# i2c_encoder_5.net
KiCad netlist of a schematic drawn in EAGLE
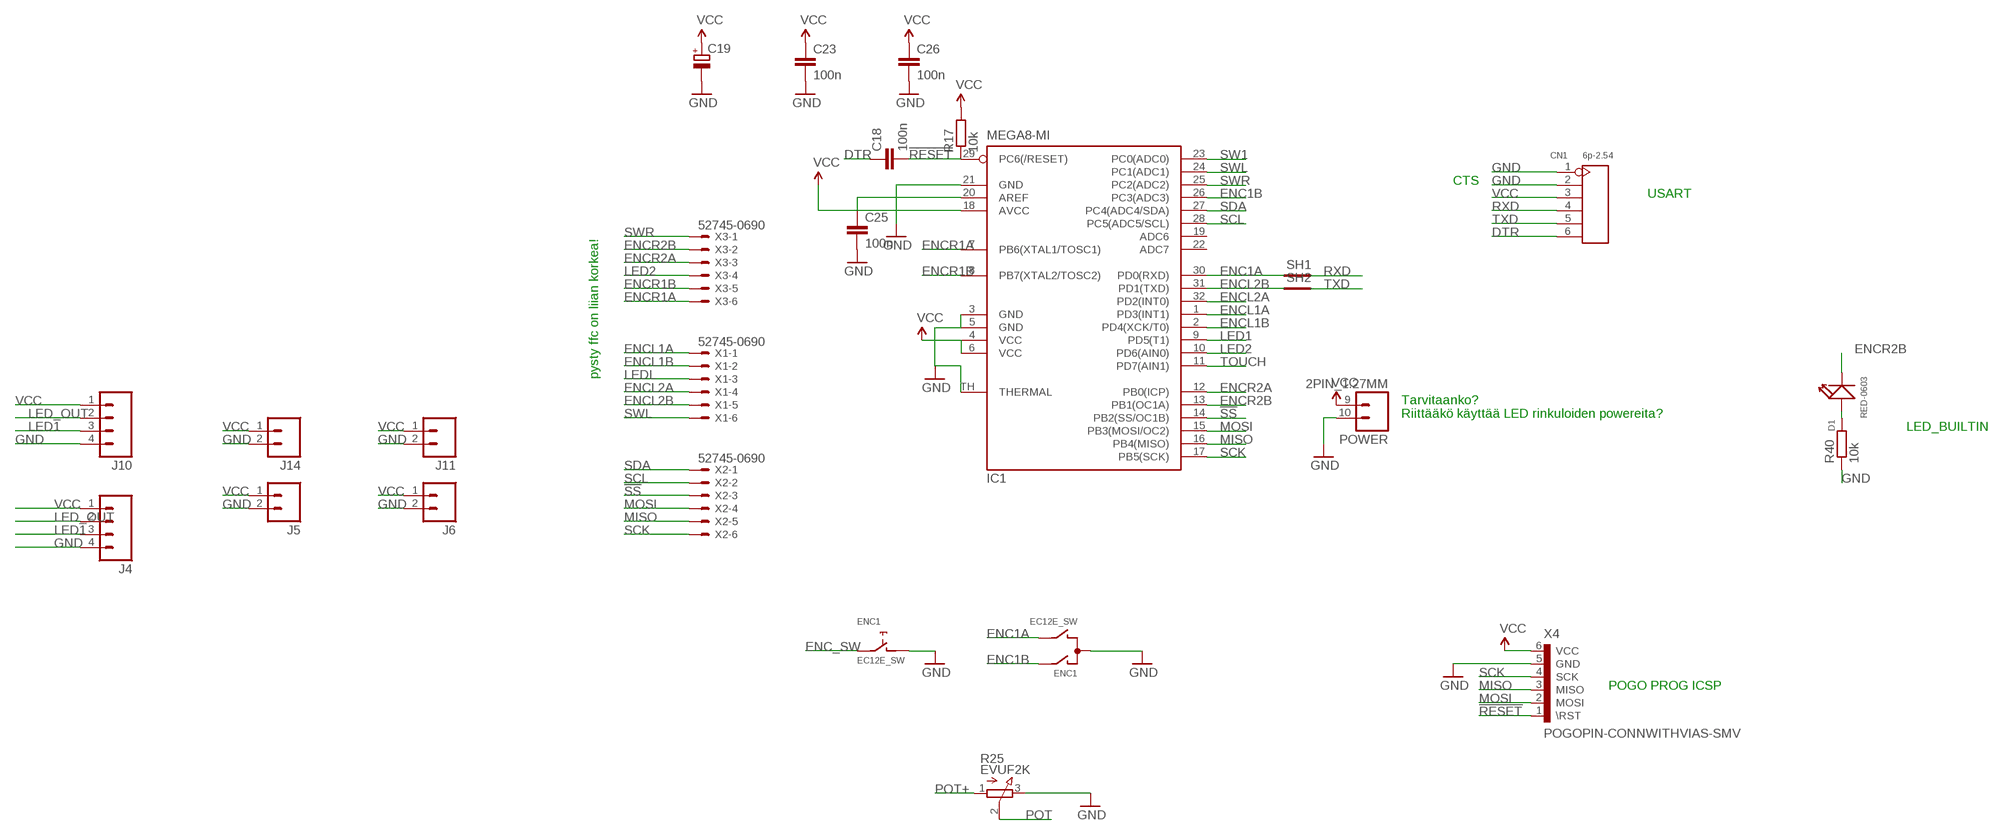
[diagram p0: schematic, sheet 1]
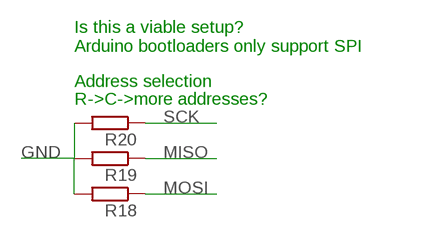
[diagram p1: schematic, sheet 2]
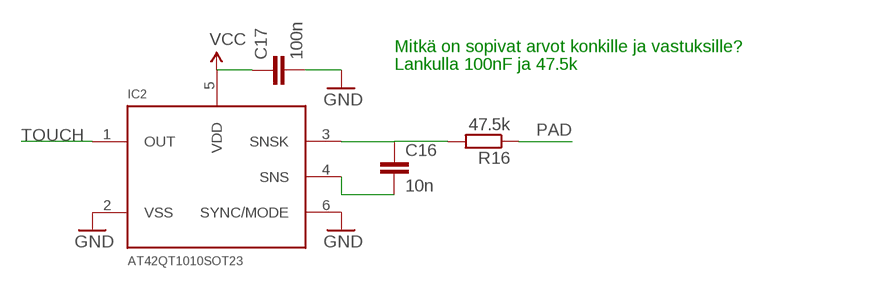
[diagram p2: schematic, sheet 3]
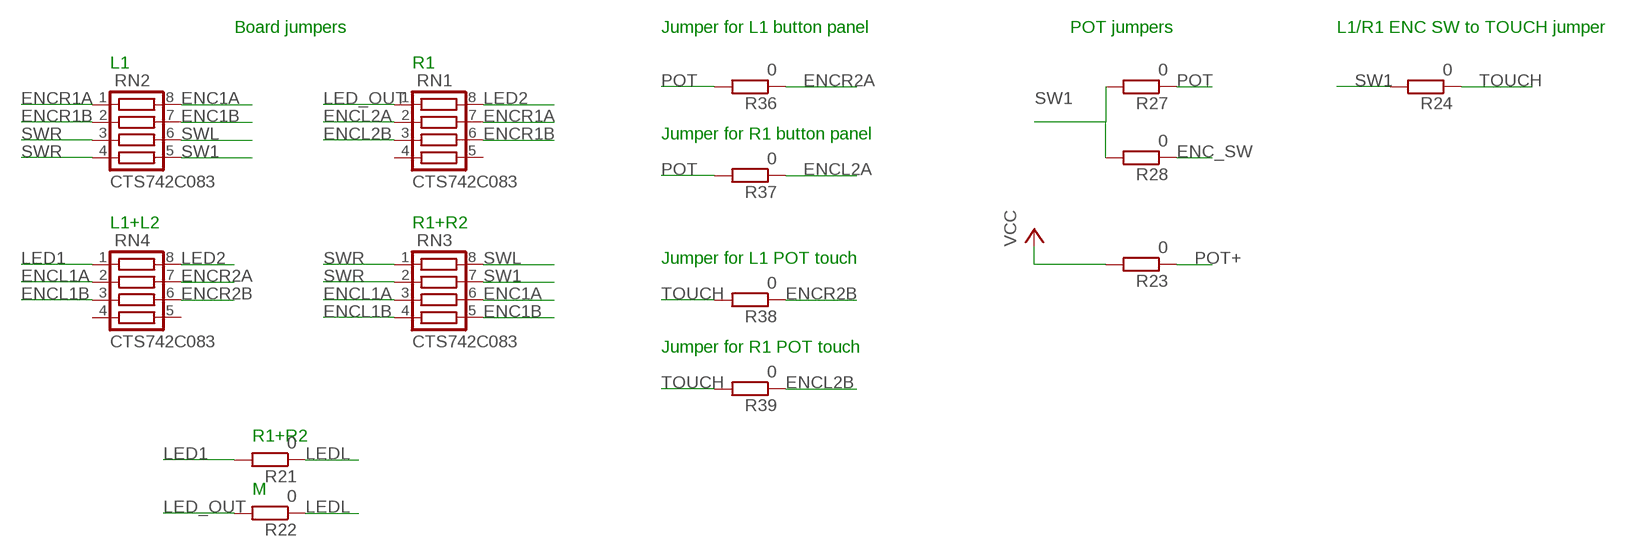
[diagram p3: schematic, sheet 4]
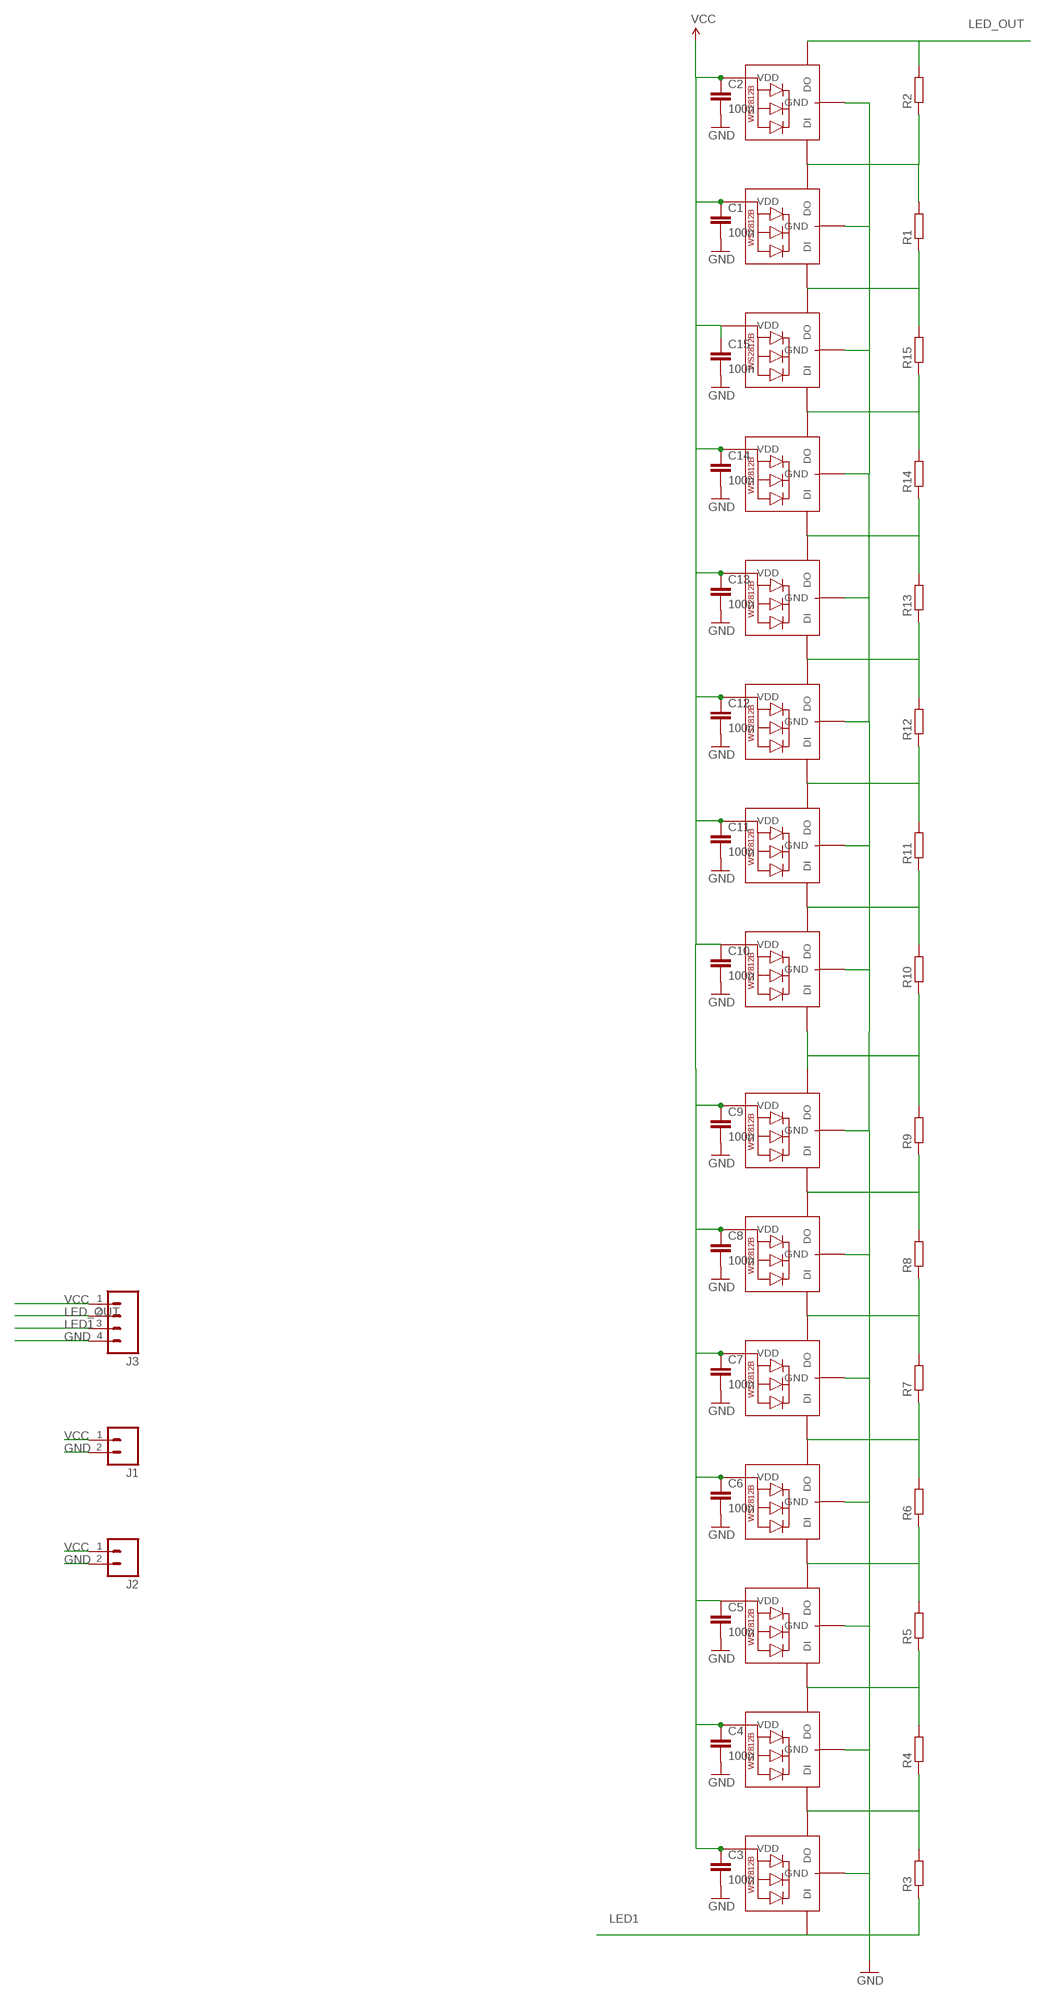
[diagram p4: schematic, sheet 5]
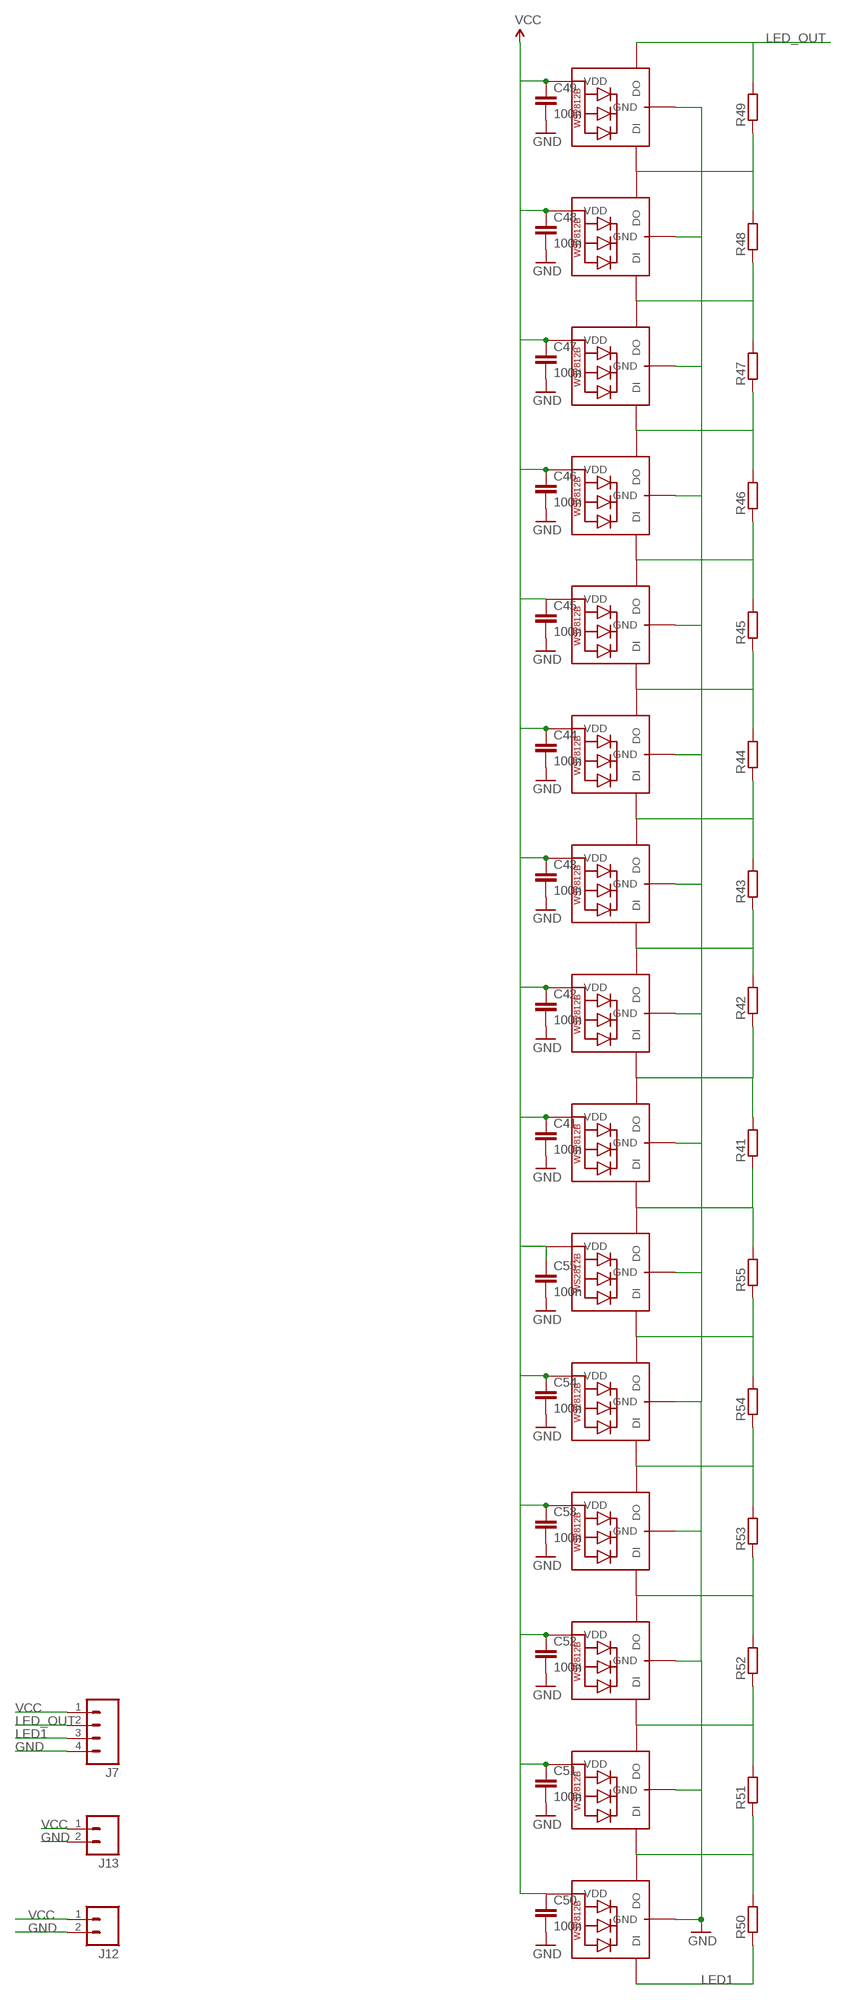
[diagram p5: schematic, sheet 6]
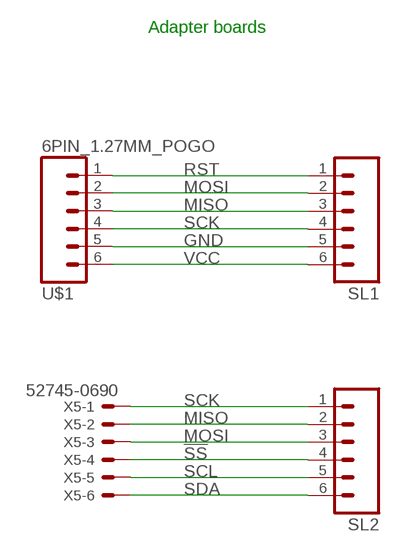
[diagram p6: schematic, sheet 7]
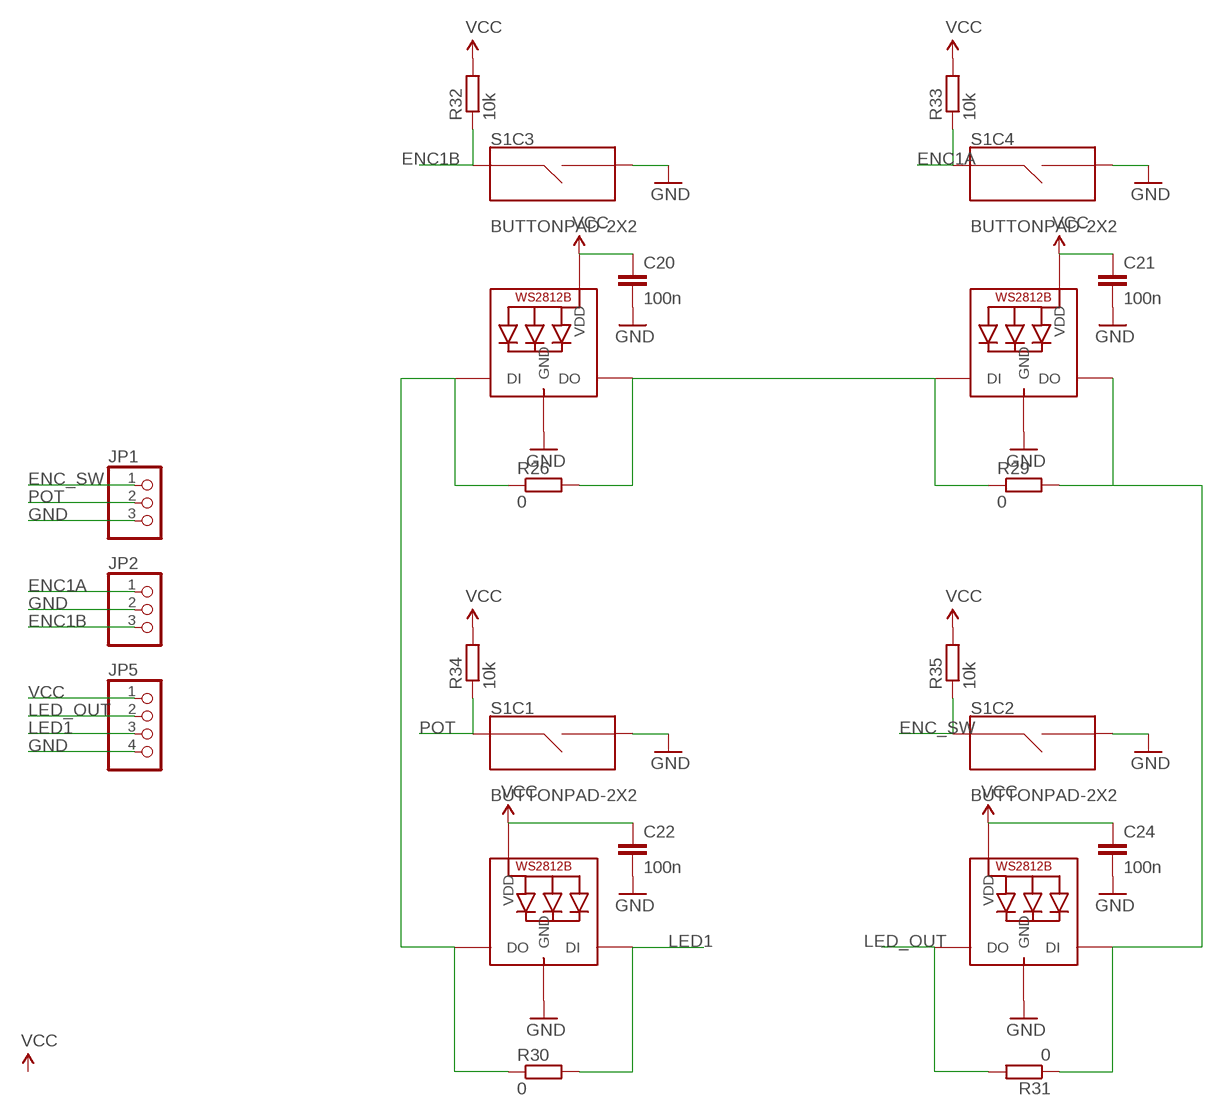
[diagram p7: schematic, sheet 8]

(export (version "E")
  (design (tool "Eeschema 10.0.6"))
  (components
    (comp (ref "R18")
      (value "R-EU_R0603")
      (footprint "eagle-import:R0603")
      (libsource (lib "eagle-import") (part "R-EU_R0603"))
    )
    (comp (ref "R19")
      (value "R-EU_R0603")
      (footprint "eagle-import:R0603")
      (libsource (lib "eagle-import") (part "R-EU_R0603"))
    )
    (comp (ref "R20")
      (value "R-EU_R0603")
      (footprint "eagle-import:R0603")
      (libsource (lib "eagle-import") (part "R-EU_R0603"))
    )
    (comp (ref "C41")
      (value "100n")
      (footprint "eagle-import:0603-CAP")
      (libsource (lib "eagle-import") (part "CAP0603-CAP"))
    )
    (comp (ref "C42")
      (value "100n")
      (footprint "eagle-import:0603-CAP")
      (libsource (lib "eagle-import") (part "CAP0603-CAP"))
    )
    (comp (ref "C43")
      (value "100n")
      (footprint "eagle-import:0603-CAP")
      (libsource (lib "eagle-import") (part "CAP0603-CAP"))
    )
    (comp (ref "C44")
      (value "100n")
      (footprint "eagle-import:0603-CAP")
      (libsource (lib "eagle-import") (part "CAP0603-CAP"))
    )
    (comp (ref "C45")
      (value "100n")
      (footprint "eagle-import:0603-CAP")
      (libsource (lib "eagle-import") (part "CAP0603-CAP"))
    )
    (comp (ref "C46")
      (value "100n")
      (footprint "eagle-import:0603-CAP")
      (libsource (lib "eagle-import") (part "CAP0603-CAP"))
    )
    (comp (ref "C47")
      (value "100n")
      (footprint "eagle-import:0603-CAP")
      (libsource (lib "eagle-import") (part "CAP0603-CAP"))
    )
    (comp (ref "C48")
      (value "100n")
      (footprint "eagle-import:0603-CAP")
      (libsource (lib "eagle-import") (part "CAP0603-CAP"))
    )
    (comp (ref "C49")
      (value "100n")
      (footprint "eagle-import:0603-CAP")
      (libsource (lib "eagle-import") (part "CAP0603-CAP"))
    )
    (comp (ref "C50")
      (value "100n")
      (footprint "eagle-import:0603-CAP")
      (libsource (lib "eagle-import") (part "CAP0603-CAP"))
    )
    (comp (ref "C51")
      (value "100n")
      (footprint "eagle-import:0603-CAP")
      (libsource (lib "eagle-import") (part "CAP0603-CAP"))
    )
    (comp (ref "C52")
      (value "100n")
      (footprint "eagle-import:0603-CAP")
      (libsource (lib "eagle-import") (part "CAP0603-CAP"))
    )
    (comp (ref "C53")
      (value "100n")
      (footprint "eagle-import:0603-CAP")
      (libsource (lib "eagle-import") (part "CAP0603-CAP"))
    )
    (comp (ref "C54")
      (value "100n")
      (footprint "eagle-import:0603-CAP")
      (libsource (lib "eagle-import") (part "CAP0603-CAP"))
    )
    (comp (ref "C55")
      (value "100n")
      (footprint "eagle-import:0603-CAP")
      (libsource (lib "eagle-import") (part "CAP0603-CAP"))
    )
    (comp (ref "J7")
      (value "M04NO_SILK_ALL_ROUND")
      (footprint "eagle-import:1X04_NO_SILK_ALL_ROUND")
      (libsource (lib "eagle-import") (part "M04NO_SILK_ALL_ROUND"))
    )
    (comp (ref "J12")
      (value "M021X02_NO_SILK")
      (footprint "eagle-import:1X02_NO_SILK")
      (libsource (lib "eagle-import") (part "M021X02_NO_SILK"))
    )
    (comp (ref "J13")
      (value "M021X02_NO_SILK")
      (footprint "eagle-import:1X02_NO_SILK")
      (libsource (lib "eagle-import") (part "M021X02_NO_SILK"))
    )
    (comp (ref "LED31")
      (value "WS2812B3535")
      (footprint "eagle-import:LED3535")
      (libsource (lib "eagle-import") (part "WS2812B3535"))
    )
    (comp (ref "LED32")
      (value "WS2812B3535")
      (footprint "eagle-import:LED3535")
      (libsource (lib "eagle-import") (part "WS2812B3535"))
    )
    (comp (ref "LED33")
      (value "WS2812B3535")
      (footprint "eagle-import:LED3535")
      (libsource (lib "eagle-import") (part "WS2812B3535"))
    )
    (comp (ref "LED34")
      (value "WS2812B3535")
      (footprint "eagle-import:LED3535")
      (libsource (lib "eagle-import") (part "WS2812B3535"))
    )
    (comp (ref "LED35")
      (value "WS2812B3535")
      (footprint "eagle-import:LED3535")
      (libsource (lib "eagle-import") (part "WS2812B3535"))
    )
    (comp (ref "LED36")
      (value "WS2812B3535")
      (footprint "eagle-import:LED3535")
      (libsource (lib "eagle-import") (part "WS2812B3535"))
    )
    (comp (ref "LED37")
      (value "WS2812B3535")
      (footprint "eagle-import:LED3535")
      (libsource (lib "eagle-import") (part "WS2812B3535"))
    )
    (comp (ref "LED38")
      (value "WS2812B3535")
      (footprint "eagle-import:LED3535")
      (libsource (lib "eagle-import") (part "WS2812B3535"))
    )
    (comp (ref "LED39")
      (value "WS2812B3535")
      (footprint "eagle-import:LED3535")
      (libsource (lib "eagle-import") (part "WS2812B3535"))
    )
    (comp (ref "LED40")
      (value "WS2812B3535")
      (footprint "eagle-import:LED3535")
      (libsource (lib "eagle-import") (part "WS2812B3535"))
    )
    (comp (ref "LED41")
      (value "WS2812B3535")
      (footprint "eagle-import:LED3535")
      (libsource (lib "eagle-import") (part "WS2812B3535"))
    )
    (comp (ref "LED42")
      (value "WS2812B3535")
      (footprint "eagle-import:LED3535")
      (libsource (lib "eagle-import") (part "WS2812B3535"))
    )
    (comp (ref "LED43")
      (value "WS2812B3535")
      (footprint "eagle-import:LED3535")
      (libsource (lib "eagle-import") (part "WS2812B3535"))
    )
    (comp (ref "LED44")
      (value "WS2812B3535")
      (footprint "eagle-import:LED3535")
      (libsource (lib "eagle-import") (part "WS2812B3535"))
    )
    (comp (ref "LED45")
      (value "WS2812B3535")
      (footprint "eagle-import:LED3535")
      (libsource (lib "eagle-import") (part "WS2812B3535"))
    )
    (comp (ref "R41")
      (value "R-EU_R0603")
      (footprint "eagle-import:R0603")
      (libsource (lib "eagle-import") (part "R-EU_R0603"))
    )
    (comp (ref "R42")
      (value "R-EU_R0603")
      (footprint "eagle-import:R0603")
      (libsource (lib "eagle-import") (part "R-EU_R0603"))
    )
    (comp (ref "R43")
      (value "R-EU_R0603")
      (footprint "eagle-import:R0603")
      (libsource (lib "eagle-import") (part "R-EU_R0603"))
    )
    (comp (ref "R44")
      (value "R-EU_R0603")
      (footprint "eagle-import:R0603")
      (libsource (lib "eagle-import") (part "R-EU_R0603"))
    )
    (comp (ref "R45")
      (value "R-EU_R0603")
      (footprint "eagle-import:R0603")
      (libsource (lib "eagle-import") (part "R-EU_R0603"))
    )
    (comp (ref "R46")
      (value "R-EU_R0603")
      (footprint "eagle-import:R0603")
      (libsource (lib "eagle-import") (part "R-EU_R0603"))
    )
    (comp (ref "R47")
      (value "R-EU_R0603")
      (footprint "eagle-import:R0603")
      (libsource (lib "eagle-import") (part "R-EU_R0603"))
    )
    (comp (ref "R48")
      (value "R-EU_R0603")
      (footprint "eagle-import:R0603")
      (libsource (lib "eagle-import") (part "R-EU_R0603"))
    )
    (comp (ref "R49")
      (value "R-EU_R0603")
      (footprint "eagle-import:R0603")
      (libsource (lib "eagle-import") (part "R-EU_R0603"))
    )
    (comp (ref "R50")
      (value "R-EU_R0603")
      (footprint "eagle-import:R0603")
      (libsource (lib "eagle-import") (part "R-EU_R0603"))
    )
    (comp (ref "R51")
      (value "R-EU_R0603")
      (footprint "eagle-import:R0603")
      (libsource (lib "eagle-import") (part "R-EU_R0603"))
    )
    (comp (ref "R52")
      (value "R-EU_R0603")
      (footprint "eagle-import:R0603")
      (libsource (lib "eagle-import") (part "R-EU_R0603"))
    )
    (comp (ref "R53")
      (value "R-EU_R0603")
      (footprint "eagle-import:R0603")
      (libsource (lib "eagle-import") (part "R-EU_R0603"))
    )
    (comp (ref "R54")
      (value "R-EU_R0603")
      (footprint "eagle-import:R0603")
      (libsource (lib "eagle-import") (part "R-EU_R0603"))
    )
    (comp (ref "R55")
      (value "R-EU_R0603")
      (footprint "eagle-import:R0603")
      (libsource (lib "eagle-import") (part "R-EU_R0603"))
    )
    (comp (ref "C16")
      (value "10n")
      (footprint "eagle-import:0603-CAP")
      (libsource (lib "eagle-import") (part "CAP0603-CAP"))
    )
    (comp (ref "C17")
      (value "100n")
      (footprint "eagle-import:0603-CAP")
      (libsource (lib "eagle-import") (part "CAP0603-CAP"))
    )
    (comp (ref "IC2")
      (value "AT42QT1010SOT23")
      (footprint "eagle-import:SOT23-6")
      (libsource (lib "eagle-import") (part "AT42QT1010SOT23"))
    )
    (comp (ref "R16")
      (value "47.5k")
      (footprint "eagle-import:R0603")
      (libsource (lib "eagle-import") (part "R-EU_R0603"))
    )
    (comp (ref "R21")
      (value "0")
      (footprint "eagle-import:R0603")
      (libsource (lib "eagle-import") (part "R-EU_R0603"))
    )
    (comp (ref "R22")
      (value "0")
      (footprint "eagle-import:R0603")
      (fields (field (name "SPICEPREFIX") "R"))
      (libsource (lib "eagle-import") (part "R-EU_R0603"))
    )
    (comp (ref "R23")
      (value "0")
      (footprint "eagle-import:R0603")
      (fields (field (name "SPICEPREFIX") "R"))
      (libsource (lib "eagle-import") (part "R-EU_R0603"))
    )
    (comp (ref "R24")
      (value "0")
      (footprint "eagle-import:R0603")
      (fields (field (name "SPICEPREFIX") "R"))
      (libsource (lib "eagle-import") (part "R-EU_R0603"))
    )
    (comp (ref "R27")
      (value "0")
      (footprint "eagle-import:R0603")
      (fields (field (name "SPICEPREFIX") "R"))
      (libsource (lib "eagle-import") (part "R-EU_R0603"))
    )
    (comp (ref "R28")
      (value "0")
      (footprint "eagle-import:R0603")
      (fields (field (name "SPICEPREFIX") "R"))
      (libsource (lib "eagle-import") (part "R-EU_R0603"))
    )
    (comp (ref "R36")
      (value "0")
      (footprint "eagle-import:R0603")
      (fields (field (name "SPICEPREFIX") "R"))
      (libsource (lib "eagle-import") (part "R-EU_R0603"))
    )
    (comp (ref "R37")
      (value "0")
      (footprint "eagle-import:R0603")
      (fields (field (name "SPICEPREFIX") "R"))
      (libsource (lib "eagle-import") (part "R-EU_R0603"))
    )
    (comp (ref "R38")
      (value "0")
      (footprint "eagle-import:R0603")
      (fields (field (name "SPICEPREFIX") "R"))
      (libsource (lib "eagle-import") (part "R-EU_R0603"))
    )
    (comp (ref "R39")
      (value "0")
      (footprint "eagle-import:R0603")
      (fields (field (name "SPICEPREFIX") "R"))
      (libsource (lib "eagle-import") (part "R-EU_R0603"))
    )
    (comp (ref "RN1")
      (value "CTS742C083")
      (footprint "eagle-import:CTS742C083")
      (libsource (lib "eagle-import") (part "CTS742C083"))
    )
    (comp (ref "RN2")
      (value "CTS742C083")
      (footprint "eagle-import:CTS742C083")
      (libsource (lib "eagle-import") (part "CTS742C083"))
    )
    (comp (ref "RN3")
      (value "CTS742C083")
      (footprint "eagle-import:CTS742C083")
      (libsource (lib "eagle-import") (part "CTS742C083"))
    )
    (comp (ref "RN4")
      (value "CTS742C083")
      (footprint "eagle-import:CTS742C083")
      (libsource (lib "eagle-import") (part "CTS742C083"))
    )
    (comp (ref "C1")
      (value "100n")
      (footprint "eagle-import:0603-CAP")
      (libsource (lib "eagle-import") (part "CAP0603-CAP"))
    )
    (comp (ref "C2")
      (value "100n")
      (footprint "eagle-import:0603-CAP")
      (libsource (lib "eagle-import") (part "CAP0603-CAP"))
    )
    (comp (ref "C3")
      (value "100n")
      (footprint "eagle-import:0603-CAP")
      (libsource (lib "eagle-import") (part "CAP0603-CAP"))
    )
    (comp (ref "C4")
      (value "100n")
      (footprint "eagle-import:0603-CAP")
      (libsource (lib "eagle-import") (part "CAP0603-CAP"))
    )
    (comp (ref "C5")
      (value "100n")
      (footprint "eagle-import:0603-CAP")
      (libsource (lib "eagle-import") (part "CAP0603-CAP"))
    )
    (comp (ref "C6")
      (value "100n")
      (footprint "eagle-import:0603-CAP")
      (libsource (lib "eagle-import") (part "CAP0603-CAP"))
    )
    (comp (ref "C7")
      (value "100n")
      (footprint "eagle-import:0603-CAP")
      (libsource (lib "eagle-import") (part "CAP0603-CAP"))
    )
    (comp (ref "C8")
      (value "100n")
      (footprint "eagle-import:0603-CAP")
      (libsource (lib "eagle-import") (part "CAP0603-CAP"))
    )
    (comp (ref "C9")
      (value "100n")
      (footprint "eagle-import:0603-CAP")
      (libsource (lib "eagle-import") (part "CAP0603-CAP"))
    )
    (comp (ref "C10")
      (value "100n")
      (footprint "eagle-import:0603-CAP")
      (libsource (lib "eagle-import") (part "CAP0603-CAP"))
    )
    (comp (ref "C11")
      (value "100n")
      (footprint "eagle-import:0603-CAP")
      (libsource (lib "eagle-import") (part "CAP0603-CAP"))
    )
    (comp (ref "C12")
      (value "100n")
      (footprint "eagle-import:0603-CAP")
      (libsource (lib "eagle-import") (part "CAP0603-CAP"))
    )
    (comp (ref "C13")
      (value "100n")
      (footprint "eagle-import:0603-CAP")
      (libsource (lib "eagle-import") (part "CAP0603-CAP"))
    )
    (comp (ref "C14")
      (value "100n")
      (footprint "eagle-import:0603-CAP")
      (libsource (lib "eagle-import") (part "CAP0603-CAP"))
    )
    (comp (ref "C15")
      (value "100n")
      (footprint "eagle-import:0603-CAP")
      (libsource (lib "eagle-import") (part "CAP0603-CAP"))
    )
    (comp (ref "J1")
      (value "M021X02_NO_SILK")
      (footprint "eagle-import:1X02_NO_SILK")
      (libsource (lib "eagle-import") (part "M021X02_NO_SILK"))
    )
    (comp (ref "J2")
      (value "M021X02_NO_SILK")
      (footprint "eagle-import:1X02_NO_SILK")
      (libsource (lib "eagle-import") (part "M021X02_NO_SILK"))
    )
    (comp (ref "J3")
      (value "M04NO_SILK_ALL_ROUND")
      (footprint "eagle-import:1X04_NO_SILK_ALL_ROUND")
      (libsource (lib "eagle-import") (part "M04NO_SILK_ALL_ROUND"))
    )
    (comp (ref "LED1")
      (value "WS2812B3535")
      (footprint "eagle-import:LED3535")
      (libsource (lib "eagle-import") (part "WS2812B3535"))
    )
    (comp (ref "LED2")
      (value "WS2812B3535")
      (footprint "eagle-import:LED3535")
      (libsource (lib "eagle-import") (part "WS2812B3535"))
    )
    (comp (ref "LED3")
      (value "WS2812B3535")
      (footprint "eagle-import:LED3535")
      (libsource (lib "eagle-import") (part "WS2812B3535"))
    )
    (comp (ref "LED4")
      (value "WS2812B3535")
      (footprint "eagle-import:LED3535")
      (fields (field (name "SPICEPREFIX") "E"))
      (libsource (lib "eagle-import") (part "WS2812B3535"))
    )
    (comp (ref "LED5")
      (value "WS2812B3535")
      (footprint "eagle-import:LED3535")
      (libsource (lib "eagle-import") (part "WS2812B3535"))
    )
    (comp (ref "LED6")
      (value "WS2812B3535")
      (footprint "eagle-import:LED3535")
      (libsource (lib "eagle-import") (part "WS2812B3535"))
    )
    (comp (ref "LED7")
      (value "WS2812B3535")
      (footprint "eagle-import:LED3535")
      (libsource (lib "eagle-import") (part "WS2812B3535"))
    )
    (comp (ref "LED8")
      (value "WS2812B3535")
      (footprint "eagle-import:LED3535")
      (libsource (lib "eagle-import") (part "WS2812B3535"))
    )
    (comp (ref "LED9")
      (value "WS2812B3535")
      (footprint "eagle-import:LED3535")
      (libsource (lib "eagle-import") (part "WS2812B3535"))
    )
    (comp (ref "LED10")
      (value "WS2812B3535")
      (footprint "eagle-import:LED3535")
      (libsource (lib "eagle-import") (part "WS2812B3535"))
    )
    (comp (ref "LED11")
      (value "WS2812B3535")
      (footprint "eagle-import:LED3535")
      (libsource (lib "eagle-import") (part "WS2812B3535"))
    )
    (comp (ref "LED12")
      (value "WS2812B3535")
      (footprint "eagle-import:LED3535")
      (libsource (lib "eagle-import") (part "WS2812B3535"))
    )
    (comp (ref "LED13")
      (value "WS2812B3535")
      (footprint "eagle-import:LED3535")
      (libsource (lib "eagle-import") (part "WS2812B3535"))
    )
    (comp (ref "LED14")
      (value "WS2812B3535")
      (footprint "eagle-import:LED3535")
      (libsource (lib "eagle-import") (part "WS2812B3535"))
    )
    (comp (ref "LED15")
      (value "WS2812B3535")
      (footprint "eagle-import:LED3535")
      (libsource (lib "eagle-import") (part "WS2812B3535"))
    )
    (comp (ref "R1")
      (value "R-EU_R0603")
      (footprint "eagle-import:R0603")
      (libsource (lib "eagle-import") (part "R-EU_R0603"))
    )
    (comp (ref "R2")
      (value "R-EU_R0603")
      (footprint "eagle-import:R0603")
      (libsource (lib "eagle-import") (part "R-EU_R0603"))
    )
    (comp (ref "R3")
      (value "R-EU_R0603")
      (footprint "eagle-import:R0603")
      (libsource (lib "eagle-import") (part "R-EU_R0603"))
    )
    (comp (ref "R4")
      (value "R-EU_R0603")
      (footprint "eagle-import:R0603")
      (libsource (lib "eagle-import") (part "R-EU_R0603"))
    )
    (comp (ref "R5")
      (value "R-EU_R0603")
      (footprint "eagle-import:R0603")
      (libsource (lib "eagle-import") (part "R-EU_R0603"))
    )
    (comp (ref "R6")
      (value "R-EU_R0603")
      (footprint "eagle-import:R0603")
      (libsource (lib "eagle-import") (part "R-EU_R0603"))
    )
    (comp (ref "R7")
      (value "R-EU_R0603")
      (footprint "eagle-import:R0603")
      (libsource (lib "eagle-import") (part "R-EU_R0603"))
    )
    (comp (ref "R8")
      (value "R-EU_R0603")
      (footprint "eagle-import:R0603")
      (libsource (lib "eagle-import") (part "R-EU_R0603"))
    )
    (comp (ref "R9")
      (value "R-EU_R0603")
      (footprint "eagle-import:R0603")
      (libsource (lib "eagle-import") (part "R-EU_R0603"))
    )
    (comp (ref "R10")
      (value "R-EU_R0603")
      (footprint "eagle-import:R0603")
      (libsource (lib "eagle-import") (part "R-EU_R0603"))
    )
    (comp (ref "R11")
      (value "R-EU_R0603")
      (footprint "eagle-import:R0603")
      (libsource (lib "eagle-import") (part "R-EU_R0603"))
    )
    (comp (ref "R12")
      (value "R-EU_R0603")
      (footprint "eagle-import:R0603")
      (libsource (lib "eagle-import") (part "R-EU_R0603"))
    )
    (comp (ref "R13")
      (value "R-EU_R0603")
      (footprint "eagle-import:R0603")
      (libsource (lib "eagle-import") (part "R-EU_R0603"))
    )
    (comp (ref "R14")
      (value "R-EU_R0603")
      (footprint "eagle-import:R0603")
      (libsource (lib "eagle-import") (part "R-EU_R0603"))
    )
    (comp (ref "R15")
      (value "R-EU_R0603")
      (footprint "eagle-import:R0603")
      (libsource (lib "eagle-import") (part "R-EU_R0603"))
    )
    (comp (ref "SL1")
      (value "M06")
      (footprint "eagle-import:06P")
      (libsource (lib "eagle-import") (part "M06"))
    )
    (comp (ref "SL2")
      (value "M06")
      (footprint "eagle-import:06P")
      (libsource (lib "eagle-import") (part "M06"))
    )
    (comp (ref "U$1")
      (value "6PIN_1.27MM_POGO")
      (footprint "eagle-import:1X06-1.27MM_POGO")
      (libsource (lib "eagle-import") (part "6PIN_1.27MM_POGO"))
    )
    (comp (ref "X5")
      (value "52745-0690")
      (footprint "eagle-import:52745-0690")
      (fields (field (name "MF") "MOLEX"))
      (libsource (lib "eagle-import") (part "52745-0690"))
    )
    (comp (ref "C18")
      (value "100n")
      (footprint "eagle-import:0603-CAP")
      (libsource (lib "eagle-import") (part "CAP0603-CAP"))
    )
    (comp (ref "C19")
      (value "CPOL-EUC")
      (footprint "eagle-import:PANASONIC_C")
      (libsource (lib "eagle-import") (part "CPOL-EUC"))
    )
    (comp (ref "C23")
      (value "100n")
      (footprint "eagle-import:0603-CAP")
      (libsource (lib "eagle-import") (part "CAP0603-CAP"))
    )
    (comp (ref "C25")
      (value "100n")
      (footprint "eagle-import:0603-CAP")
      (libsource (lib "eagle-import") (part "CAP0603-CAP"))
    )
    (comp (ref "C26")
      (value "100n")
      (footprint "eagle-import:0603-CAP")
      (libsource (lib "eagle-import") (part "CAP0603-CAP"))
    )
    (comp (ref "CN1")
      (value "6p-2.54")
      (footprint "eagle-import:H6-2.54")
      (fields (field (name "MPN") "F185-1106A1BSYC1"))
      (libsource (lib "eagle-import") (part "DIP-BLACK-FEMALE-HEADER-VERT(6P-2.54)"))
    )
    (comp (ref "D1")
      (value "RED-0603")
      (footprint "eagle-import:LED-0603")
      (fields (field (name "MPN") "19-217-R6C-AL1M2VY-3T"))
      (libsource (lib "eagle-import") (part "LED-SMD-RED-DIFFUSED(0603)"))
    )
    (comp (ref "ENC1")
      (value "EC12E_SW")
      (footprint "eagle-import:ALPS_EC12E_SW")
      (fields (field (name "MPN") "EC12E2424407"))
      (libsource (lib "eagle-import") (part "EC12E_SW"))
    )
    (comp (ref "IC1")
      (value "MEGA8-MI")
      (footprint "eagle-import:MLF32-TH")
      (fields (field (name "MPN") "ATMEGA88PA-MU"))
      (libsource (lib "eagle-import") (part "MEGA8-MI"))
    )
    (comp (ref "J4")
      (value "M04NO_SILK_ALL_ROUND")
      (footprint "eagle-import:1X04_NO_SILK_ALL_ROUND")
      (libsource (lib "eagle-import") (part "M04NO_SILK_ALL_ROUND"))
    )
    (comp (ref "J5")
      (value "M021X02_NO_SILK")
      (footprint "eagle-import:1X02_NO_SILK")
      (libsource (lib "eagle-import") (part "M021X02_NO_SILK"))
    )
    (comp (ref "J6")
      (value "M021X02_NO_SILK")
      (footprint "eagle-import:1X02_NO_SILK")
      (libsource (lib "eagle-import") (part "M021X02_NO_SILK"))
    )
    (comp (ref "J10")
      (value "M04NO_SILK_ALL_ROUND")
      (footprint "eagle-import:1X04_NO_SILK_ALL_ROUND")
      (libsource (lib "eagle-import") (part "M04NO_SILK_ALL_ROUND"))
    )
    (comp (ref "J11")
      (value "M021X02_NO_SILK")
      (footprint "eagle-import:1X02_NO_SILK")
      (libsource (lib "eagle-import") (part "M021X02_NO_SILK"))
    )
    (comp (ref "J14")
      (value "M021X02_NO_SILK")
      (footprint "eagle-import:1X02_NO_SILK")
      (libsource (lib "eagle-import") (part "M021X02_NO_SILK"))
    )
    (comp (ref "POWER")
      (value "2PIN_1.27MM")
      (footprint "eagle-import:1X02_1.27MM_NO_SILK")
      (libsource (lib "eagle-import") (part "2PIN_1.27MM"))
    )
    (comp (ref "R17")
      (value "10k")
      (footprint "eagle-import:R0603")
      (libsource (lib "eagle-import") (part "R-EU_R0603"))
    )
    (comp (ref "R25")
      (value "EVUF2K")
      (footprint "eagle-import:EVUFXK")
      (libsource (lib "eagle-import") (part "EVUF2K"))
    )
    (comp (ref "R40")
      (value "10k")
      (footprint "eagle-import:R0603")
      (libsource (lib "eagle-import") (part "R-EU_R0603"))
    )
    (comp (ref "SH1")
      (value "SHORT")
      (footprint "eagle-import:SHORT_TOP_8MIL")
      (libsource (lib "eagle-import") (part "SHORT"))
    )
    (comp (ref "SH2")
      (value "SHORT")
      (footprint "eagle-import:SHORT_TOP_8MIL")
      (libsource (lib "eagle-import") (part "SHORT"))
    )
    (comp (ref "X1")
      (value "52745-0690")
      (footprint "eagle-import:52745-0690")
      (fields (field (name "MF") "MOLEX"))
      (libsource (lib "eagle-import") (part "52745-0690"))
    )
    (comp (ref "X2")
      (value "52745-0690")
      (footprint "eagle-import:52745-0690")
      (fields (field (name "MF") "MOLEX"))
      (libsource (lib "eagle-import") (part "52745-0690"))
    )
    (comp (ref "X3")
      (value "52745-0690")
      (footprint "eagle-import:52745-0690")
      (fields (field (name "MF") "MOLEX"))
      (libsource (lib "eagle-import") (part "52745-0690"))
    )
    (comp (ref "X4")
      (value "POGOPIN-CONNWITHVIAS-SMV")
      (footprint "eagle-import:POGOPROG-CONN-OH-SMALLERVIAS")
      (libsource (lib "eagle-import") (part "POGOPIN-CONNWITHVIAS-SMV"))
    )
    (comp (ref "C20")
      (value "100n")
      (footprint "eagle-import:0603-CAP")
      (libsource (lib "eagle-import") (part "CAP0603-CAP"))
    )
    (comp (ref "C21")
      (value "100n")
      (footprint "eagle-import:0603-CAP")
      (libsource (lib "eagle-import") (part "CAP0603-CAP"))
    )
    (comp (ref "C22")
      (value "100n")
      (footprint "eagle-import:0603-CAP")
      (libsource (lib "eagle-import") (part "CAP0603-CAP"))
    )
    (comp (ref "C24")
      (value "100n")
      (footprint "eagle-import:0603-CAP")
      (libsource (lib "eagle-import") (part "CAP0603-CAP"))
    )
    (comp (ref "JP1")
      (value "PINHD-1X31X03_SMT")
      (footprint "eagle-import:1X03_SMT")
      (libsource (lib "eagle-import") (part "PINHD-1X31X03_SMT"))
    )
    (comp (ref "JP2")
      (value "PINHD-1X31X03_SMT")
      (footprint "eagle-import:1X03_SMT")
      (libsource (lib "eagle-import") (part "PINHD-1X31X03_SMT"))
    )
    (comp (ref "JP5")
      (value "PINHD-1X41X04_SMT")
      (footprint "eagle-import:1X04_SMT")
      (libsource (lib "eagle-import") (part "PINHD-1X41X04_SMT"))
    )
    (comp (ref "LED16")
      (value "WS2812B3535")
      (footprint "eagle-import:LED3535")
      (libsource (lib "eagle-import") (part "WS2812B3535"))
    )
    (comp (ref "LED17")
      (value "WS2812B3535")
      (footprint "eagle-import:LED3535")
      (libsource (lib "eagle-import") (part "WS2812B3535"))
    )
    (comp (ref "LED18")
      (value "WS2812B3535")
      (footprint "eagle-import:LED3535")
      (libsource (lib "eagle-import") (part "WS2812B3535"))
    )
    (comp (ref "LED19")
      (value "WS2812B3535")
      (footprint "eagle-import:LED3535")
      (libsource (lib "eagle-import") (part "WS2812B3535"))
    )
    (comp (ref "R26")
      (value "0")
      (footprint "eagle-import:R0603")
      (libsource (lib "eagle-import") (part "R-EU_R0603"))
    )
    (comp (ref "R29")
      (value "0")
      (footprint "eagle-import:R0603")
      (libsource (lib "eagle-import") (part "R-EU_R0603"))
    )
    (comp (ref "R30")
      (value "0")
      (footprint "eagle-import:R0603")
      (libsource (lib "eagle-import") (part "R-EU_R0603"))
    )
    (comp (ref "R31")
      (value "0")
      (footprint "eagle-import:R0603")
      (libsource (lib "eagle-import") (part "R-EU_R0603"))
    )
    (comp (ref "R32")
      (value "10k")
      (footprint "eagle-import:R0603")
      (libsource (lib "eagle-import") (part "R-EU_R0603"))
    )
    (comp (ref "R33")
      (value "10k")
      (footprint "eagle-import:R0603")
      (libsource (lib "eagle-import") (part "R-EU_R0603"))
    )
    (comp (ref "R34")
      (value "10k")
      (footprint "eagle-import:R0603")
      (libsource (lib "eagle-import") (part "R-EU_R0603"))
    )
    (comp (ref "R35")
      (value "10k")
      (footprint "eagle-import:R0603")
      (libsource (lib "eagle-import") (part "R-EU_R0603"))
    )
    (comp (ref "S1")
      (value "BUTTONPAD-2X2")
      (footprint "eagle-import:BUTTONPAD-2X2-SINGLE")
      (libsource (lib "eagle-import") (part "BUTTONPAD-2X2"))
    )
  )
  (nets
    (net (code "1") (name "DTR") (class "Default")
      (node (ref "C18") (pin "1") (pinfunction "1_1") (pintype "passive"))
      (node (ref "CN1") (pin "6") (pinfunction "6_6") (pintype "bidirectional"))
    )
    (net (code "2") (name "ENC1A") (class "Default")
      (node (ref "ENC1") (pin "B") (pinfunction "B_B") (pintype "passive"))
      (node (ref "IC1") (pin "30") (pinfunction "PD0(RXD)_30") (pintype "bidirectional"))
      (node (ref "JP2") (pin "1") (pinfunction "1_1") (pintype "passive"))
      (node (ref "R33") (pin "1") (pinfunction "1_1") (pintype "passive"))
      (node (ref "RN2") (pin "8") (pinfunction "8_8") (pintype "passive"))
      (node (ref "RN3") (pin "6") (pinfunction "6_6") (pintype "passive"))
      (node (ref "S1") (pin "SIG7") (pinfunction "SIG1_SIG7") (pintype "bidirectional"))
      (node (ref "SH1") (pin "P$1") (pinfunction "P$1_P$1") (pintype "bidirectional"))
    )
    (net (code "3") (name "ENC1B") (class "Default")
      (node (ref "ENC1") (pin "A") (pinfunction "A_A") (pintype "passive"))
      (node (ref "IC1") (pin "26") (pinfunction "PC3(ADC3)_26") (pintype "bidirectional"))
      (node (ref "JP2") (pin "3") (pinfunction "3_3") (pintype "passive"))
      (node (ref "R32") (pin "1") (pinfunction "1_1") (pintype "passive"))
      (node (ref "RN2") (pin "7") (pinfunction "7_7") (pintype "passive"))
      (node (ref "RN3") (pin "5") (pinfunction "5_5") (pintype "passive"))
      (node (ref "S1") (pin "SIG5") (pinfunction "SIG1_SIG5") (pintype "bidirectional"))
    )
    (net (code "4") (name "ENCL1A") (class "Default")
      (node (ref "IC1") (pin "1") (pinfunction "PD3(INT1)_1") (pintype "bidirectional"))
      (node (ref "RN3") (pin "3") (pinfunction "3_3") (pintype "passive"))
      (node (ref "RN4") (pin "2") (pinfunction "2_2") (pintype "passive"))
      (node (ref "X1") (pin "1") (pinfunction "S_1") (pintype "passive"))
    )
    (net (code "5") (name "ENCL1B") (class "Default")
      (node (ref "IC1") (pin "2") (pinfunction "PD4(XCK/T0)_2") (pintype "bidirectional"))
      (node (ref "RN3") (pin "4") (pinfunction "4_4") (pintype "passive"))
      (node (ref "RN4") (pin "3") (pinfunction "3_3") (pintype "passive"))
      (node (ref "X1") (pin "2") (pinfunction "S_2") (pintype "passive"))
    )
    (net (code "6") (name "ENCL2A") (class "Default")
      (node (ref "IC1") (pin "32") (pinfunction "PD2(INT0)_32") (pintype "bidirectional"))
      (node (ref "R37") (pin "1") (pinfunction "1_1") (pintype "passive"))
      (node (ref "RN1") (pin "2") (pinfunction "2_2") (pintype "passive"))
      (node (ref "X1") (pin "4") (pinfunction "S_4") (pintype "passive"))
    )
    (net (code "7") (name "ENCL2B") (class "Default")
      (node (ref "IC1") (pin "31") (pinfunction "PD1(TXD)_31") (pintype "bidirectional"))
      (node (ref "R39") (pin "1") (pinfunction "1_1") (pintype "passive"))
      (node (ref "RN1") (pin "3") (pinfunction "3_3") (pintype "passive"))
      (node (ref "SH2") (pin "P$1") (pinfunction "P$1_P$1") (pintype "bidirectional"))
      (node (ref "X1") (pin "5") (pinfunction "S_5") (pintype "passive"))
    )
    (net (code "8") (name "ENCR1A") (class "Default")
      (node (ref "IC1") (pin "7") (pinfunction "PB6(XTAL1/TOSC1)_7") (pintype "bidirectional"))
      (node (ref "RN1") (pin "7") (pinfunction "7_7") (pintype "passive"))
      (node (ref "RN2") (pin "1") (pinfunction "1_1") (pintype "passive"))
      (node (ref "X3") (pin "6") (pinfunction "S_6") (pintype "passive"))
    )
    (net (code "9") (name "ENCR1B") (class "Default")
      (node (ref "IC1") (pin "8") (pinfunction "PB7(XTAL2/TOSC2)_8") (pintype "bidirectional"))
      (node (ref "RN1") (pin "6") (pinfunction "6_6") (pintype "passive"))
      (node (ref "RN2") (pin "2") (pinfunction "2_2") (pintype "passive"))
      (node (ref "X3") (pin "5") (pinfunction "S_5") (pintype "passive"))
    )
    (net (code "10") (name "ENCR2A") (class "Default")
      (node (ref "IC1") (pin "12") (pinfunction "PB0(ICP)_12") (pintype "bidirectional"))
      (node (ref "R36") (pin "1") (pinfunction "1_1") (pintype "passive"))
      (node (ref "RN4") (pin "7") (pinfunction "7_7") (pintype "passive"))
      (node (ref "X3") (pin "3") (pinfunction "S_3") (pintype "passive"))
    )
    (net (code "11") (name "ENCR2B") (class "Default")
      (node (ref "D1") (pin "-") (pinfunction "-_-") (pintype "passive"))
      (node (ref "IC1") (pin "13") (pinfunction "PB1(OC1A)_13") (pintype "bidirectional"))
      (node (ref "R38") (pin "1") (pinfunction "1_1") (pintype "passive"))
      (node (ref "RN4") (pin "6") (pinfunction "6_6") (pintype "passive"))
      (node (ref "X3") (pin "2") (pinfunction "S_2") (pintype "passive"))
    )
    (net (code "12") (name "ENC_SW") (class "Default")
      (node (ref "ENC1") (pin "E") (pinfunction "2_E") (pintype "passive"))
      (node (ref "JP1") (pin "1") (pinfunction "1_1") (pintype "passive"))
      (node (ref "R28") (pin "1") (pinfunction "1_1") (pintype "passive"))
      (node (ref "R35") (pin "1") (pinfunction "1_1") (pintype "passive"))
      (node (ref "S1") (pin "SIG3") (pinfunction "SIG1_SIG3") (pintype "bidirectional"))
    )
    (net (code "13") (name "GND") (class "Default")
      (node (ref "C1") (pin "2") (pinfunction "2_2") (pintype "passive"))
      (node (ref "C10") (pin "2") (pinfunction "2_2") (pintype "passive"))
      (node (ref "C11") (pin "2") (pinfunction "2_2") (pintype "passive"))
      (node (ref "C12") (pin "2") (pinfunction "2_2") (pintype "passive"))
      (node (ref "C13") (pin "2") (pinfunction "2_2") (pintype "passive"))
      (node (ref "C14") (pin "2") (pinfunction "2_2") (pintype "passive"))
      (node (ref "C15") (pin "2") (pinfunction "2_2") (pintype "passive"))
      (node (ref "C17") (pin "2") (pinfunction "2_2") (pintype "passive"))
      (node (ref "C19") (pin "-") (pinfunction "-_-") (pintype "passive"))
      (node (ref "C2") (pin "2") (pinfunction "2_2") (pintype "passive"))
      (node (ref "C20") (pin "2") (pinfunction "2_2") (pintype "passive"))
      (node (ref "C21") (pin "2") (pinfunction "2_2") (pintype "passive"))
      (node (ref "C22") (pin "2") (pinfunction "2_2") (pintype "passive"))
      (node (ref "C23") (pin "2") (pinfunction "2_2") (pintype "passive"))
      (node (ref "C24") (pin "2") (pinfunction "2_2") (pintype "passive"))
      (node (ref "C25") (pin "2") (pinfunction "2_2") (pintype "passive"))
      (node (ref "C26") (pin "2") (pinfunction "2_2") (pintype "passive"))
      (node (ref "C3") (pin "2") (pinfunction "2_2") (pintype "passive"))
      (node (ref "C4") (pin "2") (pinfunction "2_2") (pintype "passive"))
      (node (ref "C41") (pin "2") (pinfunction "2_2") (pintype "passive"))
      (node (ref "C42") (pin "2") (pinfunction "2_2") (pintype "passive"))
      (node (ref "C43") (pin "2") (pinfunction "2_2") (pintype "passive"))
      (node (ref "C44") (pin "2") (pinfunction "2_2") (pintype "passive"))
      (node (ref "C45") (pin "2") (pinfunction "2_2") (pintype "passive"))
      (node (ref "C46") (pin "2") (pinfunction "2_2") (pintype "passive"))
      (node (ref "C47") (pin "2") (pinfunction "2_2") (pintype "passive"))
      (node (ref "C48") (pin "2") (pinfunction "2_2") (pintype "passive"))
      (node (ref "C49") (pin "2") (pinfunction "2_2") (pintype "passive"))
      (node (ref "C5") (pin "2") (pinfunction "2_2") (pintype "passive"))
      (node (ref "C50") (pin "2") (pinfunction "2_2") (pintype "passive"))
      (node (ref "C51") (pin "2") (pinfunction "2_2") (pintype "passive"))
      (node (ref "C52") (pin "2") (pinfunction "2_2") (pintype "passive"))
      (node (ref "C53") (pin "2") (pinfunction "2_2") (pintype "passive"))
      (node (ref "C54") (pin "2") (pinfunction "2_2") (pintype "passive"))
      (node (ref "C55") (pin "2") (pinfunction "2_2") (pintype "passive"))
      (node (ref "C6") (pin "2") (pinfunction "2_2") (pintype "passive"))
      (node (ref "C7") (pin "2") (pinfunction "2_2") (pintype "passive"))
      (node (ref "C8") (pin "2") (pinfunction "2_2") (pintype "passive"))
      (node (ref "C9") (pin "2") (pinfunction "2_2") (pintype "passive"))
      (node (ref "CN1") (pin "1") (pinfunction "1_1") (pintype "bidirectional"))
      (node (ref "CN1") (pin "2") (pinfunction "2_2") (pintype "bidirectional"))
      (node (ref "ENC1") (pin "C") (pinfunction "C_C") (pintype "passive"))
      (node (ref "ENC1") (pin "D") (pinfunction "1_D") (pintype "passive"))
      (node (ref "IC1") (pin "21") (pinfunction "GND_21") (pintype "power_in"))
      (node (ref "IC1") (pin "3") (pinfunction "GND_3") (pintype "power_in"))
      (node (ref "IC1") (pin "5") (pinfunction "GND_5") (pintype "power_in"))
      (node (ref "IC1") (pin "TH") (pinfunction "THERMAL_TH") (pintype "passive"))
      (node (ref "IC2") (pin "2") (pinfunction "VSS_2") (pintype "bidirectional"))
      (node (ref "IC2") (pin "6") (pinfunction "SYNC/MODE_6") (pintype "bidirectional"))
      (node (ref "J1") (pin "2") (pinfunction "2_2") (pintype "passive"))
      (node (ref "J10") (pin "4") (pinfunction "4_4") (pintype "passive"))
      (node (ref "J11") (pin "2") (pinfunction "2_2") (pintype "passive"))
      (node (ref "J12") (pin "2") (pinfunction "2_2") (pintype "passive"))
      (node (ref "J13") (pin "2") (pinfunction "2_2") (pintype "passive"))
      (node (ref "J14") (pin "2") (pinfunction "2_2") (pintype "passive"))
      (node (ref "J2") (pin "2") (pinfunction "2_2") (pintype "passive"))
      (node (ref "J3") (pin "4") (pinfunction "4_4") (pintype "passive"))
      (node (ref "J4") (pin "4") (pinfunction "4_4") (pintype "passive"))
      (node (ref "J5") (pin "2") (pinfunction "2_2") (pintype "passive"))
      (node (ref "J6") (pin "2") (pinfunction "2_2") (pintype "passive"))
      (node (ref "J7") (pin "4") (pinfunction "4_4") (pintype "passive"))
      (node (ref "JP1") (pin "3") (pinfunction "3_3") (pintype "passive"))
      (node (ref "JP2") (pin "2") (pinfunction "2_2") (pintype "passive"))
      (node (ref "JP5") (pin "4") (pinfunction "4_4") (pintype "passive"))
      (node (ref "LED1") (pin "4") (pinfunction "GND_4") (pintype "power_in"))
      (node (ref "LED10") (pin "4") (pinfunction "GND_4") (pintype "power_in"))
      (node (ref "LED11") (pin "4") (pinfunction "GND_4") (pintype "power_in"))
      (node (ref "LED12") (pin "4") (pinfunction "GND_4") (pintype "power_in"))
      (node (ref "LED13") (pin "4") (pinfunction "GND_4") (pintype "power_in"))
      (node (ref "LED14") (pin "4") (pinfunction "GND_4") (pintype "power_in"))
      (node (ref "LED15") (pin "4") (pinfunction "GND_4") (pintype "power_in"))
      (node (ref "LED16") (pin "4") (pinfunction "GND_4") (pintype "power_in"))
      (node (ref "LED17") (pin "4") (pinfunction "GND_4") (pintype "power_in"))
      (node (ref "LED18") (pin "4") (pinfunction "GND_4") (pintype "power_in"))
      (node (ref "LED19") (pin "4") (pinfunction "GND_4") (pintype "power_in"))
      (node (ref "LED2") (pin "4") (pinfunction "GND_4") (pintype "power_in"))
      (node (ref "LED3") (pin "4") (pinfunction "GND_4") (pintype "power_in"))
      (node (ref "LED31") (pin "4") (pinfunction "GND_4") (pintype "power_in"))
      (node (ref "LED32") (pin "4") (pinfunction "GND_4") (pintype "power_in"))
      (node (ref "LED33") (pin "4") (pinfunction "GND_4") (pintype "power_in"))
      (node (ref "LED34") (pin "4") (pinfunction "GND_4") (pintype "power_in"))
      (node (ref "LED35") (pin "4") (pinfunction "GND_4") (pintype "power_in"))
      (node (ref "LED36") (pin "4") (pinfunction "GND_4") (pintype "power_in"))
      (node (ref "LED37") (pin "4") (pinfunction "GND_4") (pintype "power_in"))
      (node (ref "LED38") (pin "4") (pinfunction "GND_4") (pintype "power_in"))
      (node (ref "LED39") (pin "4") (pinfunction "GND_4") (pintype "power_in"))
      (node (ref "LED4") (pin "4") (pinfunction "GND_4") (pintype "power_in"))
      (node (ref "LED40") (pin "4") (pinfunction "GND_4") (pintype "power_in"))
      (node (ref "LED41") (pin "4") (pinfunction "GND_4") (pintype "power_in"))
      (node (ref "LED42") (pin "4") (pinfunction "GND_4") (pintype "power_in"))
      (node (ref "LED43") (pin "4") (pinfunction "GND_4") (pintype "power_in"))
      (node (ref "LED44") (pin "4") (pinfunction "GND_4") (pintype "power_in"))
      (node (ref "LED45") (pin "4") (pinfunction "GND_4") (pintype "power_in"))
      (node (ref "LED5") (pin "4") (pinfunction "GND_4") (pintype "power_in"))
      (node (ref "LED6") (pin "4") (pinfunction "GND_4") (pintype "power_in"))
      (node (ref "LED7") (pin "4") (pinfunction "GND_4") (pintype "power_in"))
      (node (ref "LED8") (pin "4") (pinfunction "GND_4") (pintype "power_in"))
      (node (ref "LED9") (pin "4") (pinfunction "GND_4") (pintype "power_in"))
      (node (ref "POWER") (pin "10") (pinfunction "2_10") (pintype "passive"))
      (node (ref "R18") (pin "2") (pinfunction "2_2") (pintype "passive"))
      (node (ref "R19") (pin "2") (pinfunction "2_2") (pintype "passive"))
      (node (ref "R20") (pin "2") (pinfunction "2_2") (pintype "passive"))
      (node (ref "R25") (pin "3") (pinfunction "E_3") (pintype "passive"))
      (node (ref "R40") (pin "1") (pinfunction "1_1") (pintype "passive"))
      (node (ref "S1") (pin "SIG2") (pinfunction "SIG2_SIG2") (pintype "bidirectional"))
      (node (ref "S1") (pin "SIG4") (pinfunction "SIG2_SIG4") (pintype "bidirectional"))
      (node (ref "S1") (pin "SIG6") (pinfunction "SIG2_SIG6") (pintype "bidirectional"))
      (node (ref "S1") (pin "SIG8") (pinfunction "SIG2_SIG8") (pintype "bidirectional"))
      (node (ref "SL1") (pin "5") (pinfunction "5_5") (pintype "passive"))
      (node (ref "U$1") (pin "5") (pinfunction "5_5") (pintype "passive"))
      (node (ref "X4") (pin "5") (pinfunction "GND_5") (pintype "bidirectional"))
    )
    (net (code "14") (name "LED1") (class "Default")
      (node (ref "IC1") (pin "9") (pinfunction "PD5(T1)_9") (pintype "bidirectional"))
      (node (ref "J10") (pin "3") (pinfunction "3_3") (pintype "passive"))
      (node (ref "J3") (pin "3") (pinfunction "3_3") (pintype "passive"))
      (node (ref "J4") (pin "3") (pinfunction "3_3") (pintype "passive"))
      (node (ref "J7") (pin "3") (pinfunction "3_3") (pintype "passive"))
      (node (ref "JP5") (pin "3") (pinfunction "3_3") (pintype "passive"))
      (node (ref "LED1") (pin "1") (pinfunction "DI_1") (pintype "input"))
      (node (ref "LED16") (pin "1") (pinfunction "DI_1") (pintype "input"))
      (node (ref "LED31") (pin "1") (pinfunction "DI_1") (pintype "input"))
      (node (ref "R21") (pin "2") (pinfunction "2_2") (pintype "passive"))
      (node (ref "R3") (pin "1") (pinfunction "1_1") (pintype "passive"))
      (node (ref "R30") (pin "2") (pinfunction "2_2") (pintype "passive"))
      (node (ref "R50") (pin "1") (pinfunction "1_1") (pintype "passive"))
      (node (ref "RN4") (pin "1") (pinfunction "1_1") (pintype "passive"))
    )
    (net (code "15") (name "LED2") (class "Default")
      (node (ref "IC1") (pin "10") (pinfunction "PD6(AIN0)_10") (pintype "bidirectional"))
      (node (ref "RN1") (pin "8") (pinfunction "8_8") (pintype "passive"))
      (node (ref "RN4") (pin "8") (pinfunction "8_8") (pintype "passive"))
      (node (ref "X3") (pin "4") (pinfunction "S_4") (pintype "passive"))
    )
    (net (code "16") (name "LEDL") (class "Default")
      (node (ref "R21") (pin "1") (pinfunction "1_1") (pintype "passive"))
      (node (ref "R22") (pin "1") (pinfunction "1_1") (pintype "passive"))
      (node (ref "X1") (pin "3") (pinfunction "S_3") (pintype "passive"))
    )
    (net (code "17") (name "LED_OUT") (class "Default")
      (node (ref "J10") (pin "2") (pinfunction "2_2") (pintype "passive"))
      (node (ref "J3") (pin "2") (pinfunction "2_2") (pintype "passive"))
      (node (ref "J4") (pin "2") (pinfunction "2_2") (pintype "passive"))
      (node (ref "J7") (pin "2") (pinfunction "2_2") (pintype "passive"))
      (node (ref "JP5") (pin "2") (pinfunction "2_2") (pintype "passive"))
      (node (ref "LED15") (pin "3") (pinfunction "DO_3") (pintype "output"))
      (node (ref "LED17") (pin "3") (pinfunction "DO_3") (pintype "output"))
      (node (ref "LED45") (pin "3") (pinfunction "DO_3") (pintype "output"))
      (node (ref "R2") (pin "2") (pinfunction "2_2") (pintype "passive"))
      (node (ref "R22") (pin "2") (pinfunction "2_2") (pintype "passive"))
      (node (ref "R31") (pin "2") (pinfunction "2_2") (pintype "passive"))
      (node (ref "R49") (pin "2") (pinfunction "2_2") (pintype "passive"))
      (node (ref "RN1") (pin "1") (pinfunction "1_1") (pintype "passive"))
    )
    (net (code "18") (name "MISO") (class "Default")
      (node (ref "IC1") (pin "16") (pinfunction "PB4(MISO)_16") (pintype "bidirectional"))
      (node (ref "R19") (pin "1") (pinfunction "1_1") (pintype "passive"))
      (node (ref "SL1") (pin "3") (pinfunction "3_3") (pintype "passive"))
      (node (ref "SL2") (pin "2") (pinfunction "2_2") (pintype "passive"))
      (node (ref "U$1") (pin "3") (pinfunction "3_3") (pintype "passive"))
      (node (ref "X2") (pin "5") (pinfunction "S_5") (pintype "passive"))
      (node (ref "X4") (pin "3") (pinfunction "MISO_3") (pintype "bidirectional"))
      (node (ref "X5") (pin "2") (pinfunction "S_2") (pintype "passive"))
    )
    (net (code "19") (name "MOSI") (class "Default")
      (node (ref "IC1") (pin "15") (pinfunction "PB3(MOSI/OC2)_15") (pintype "bidirectional"))
      (node (ref "R18") (pin "1") (pinfunction "1_1") (pintype "passive"))
      (node (ref "SL1") (pin "2") (pinfunction "2_2") (pintype "passive"))
      (node (ref "SL2") (pin "3") (pinfunction "3_3") (pintype "passive"))
      (node (ref "U$1") (pin "2") (pinfunction "2_2") (pintype "passive"))
      (node (ref "X2") (pin "4") (pinfunction "S_4") (pintype "passive"))
      (node (ref "X4") (pin "2") (pinfunction "MOSI_2") (pintype "bidirectional"))
      (node (ref "X5") (pin "3") (pinfunction "S_3") (pintype "passive"))
    )
    (net (code "20") (name "Net-(D1-Pad+)") (class "Default")
      (node (ref "D1") (pin "+") (pinfunction "+_+") (pintype "passive"))
      (node (ref "R40") (pin "2") (pinfunction "2_2") (pintype "passive"))
    )
    (net (code "21") (name "Net-(IC1-AREF)") (class "Default")
      (node (ref "C25") (pin "1") (pinfunction "1_1") (pintype "passive"))
      (node (ref "IC1") (pin "20") (pinfunction "AREF_20") (pintype "passive"))
    )
    (net (code "22") (name "Net-(IC2-SNS)") (class "Default")
      (node (ref "C16") (pin "2") (pinfunction "2_2") (pintype "passive"))
      (node (ref "IC2") (pin "4") (pinfunction "SNS_4") (pintype "bidirectional"))
    )
    (net (code "23") (name "Net-(IC2-SNSK)") (class "Default")
      (node (ref "C16") (pin "1") (pinfunction "1_1") (pintype "passive"))
      (node (ref "IC2") (pin "3") (pinfunction "SNSK_3") (pintype "bidirectional"))
      (node (ref "R16") (pin "2") (pinfunction "2_2") (pintype "passive"))
    )
    (net (code "24") (name "Net-(LED1-DO)") (class "Default")
      (node (ref "LED1") (pin "3") (pinfunction "DO_3") (pintype "output"))
      (node (ref "LED2") (pin "1") (pinfunction "DI_1") (pintype "input"))
      (node (ref "R3") (pin "2") (pinfunction "2_2") (pintype "passive"))
      (node (ref "R4") (pin "1") (pinfunction "1_1") (pintype "passive"))
    )
    (net (code "25") (name "Net-(LED2-DO)") (class "Default")
      (node (ref "LED2") (pin "3") (pinfunction "DO_3") (pintype "output"))
      (node (ref "LED3") (pin "1") (pinfunction "DI_1") (pintype "input"))
      (node (ref "R4") (pin "2") (pinfunction "2_2") (pintype "passive"))
      (node (ref "R5") (pin "1") (pinfunction "1_1") (pintype "passive"))
    )
    (net (code "26") (name "Net-(LED3-DO)") (class "Default")
      (node (ref "LED3") (pin "3") (pinfunction "DO_3") (pintype "output"))
      (node (ref "LED4") (pin "1") (pinfunction "DI_1") (pintype "input"))
      (node (ref "R5") (pin "2") (pinfunction "2_2") (pintype "passive"))
      (node (ref "R6") (pin "1") (pinfunction "1_1") (pintype "passive"))
    )
    (net (code "27") (name "Net-(LED4-DO)") (class "Default")
      (node (ref "LED4") (pin "3") (pinfunction "DO_3") (pintype "output"))
      (node (ref "LED5") (pin "1") (pinfunction "DI_1") (pintype "input"))
      (node (ref "R6") (pin "2") (pinfunction "2_2") (pintype "passive"))
      (node (ref "R7") (pin "1") (pinfunction "1_1") (pintype "passive"))
    )
    (net (code "28") (name "Net-(LED5-DO)") (class "Default")
      (node (ref "LED5") (pin "3") (pinfunction "DO_3") (pintype "output"))
      (node (ref "LED6") (pin "1") (pinfunction "DI_1") (pintype "input"))
      (node (ref "R7") (pin "2") (pinfunction "2_2") (pintype "passive"))
      (node (ref "R8") (pin "1") (pinfunction "1_1") (pintype "passive"))
    )
    (net (code "29") (name "Net-(LED6-DO)") (class "Default")
      (node (ref "LED6") (pin "3") (pinfunction "DO_3") (pintype "output"))
      (node (ref "LED7") (pin "1") (pinfunction "DI_1") (pintype "input"))
      (node (ref "R8") (pin "2") (pinfunction "2_2") (pintype "passive"))
      (node (ref "R9") (pin "1") (pinfunction "1_1") (pintype "passive"))
    )
    (net (code "30") (name "Net-(LED7-DO)") (class "Default")
      (node (ref "LED7") (pin "3") (pinfunction "DO_3") (pintype "output"))
      (node (ref "LED8") (pin "1") (pinfunction "DI_1") (pintype "input"))
      (node (ref "R10") (pin "1") (pinfunction "1_1") (pintype "passive"))
      (node (ref "R9") (pin "2") (pinfunction "2_2") (pintype "passive"))
    )
    (net (code "31") (name "Net-(LED8-DO)") (class "Default")
      (node (ref "LED8") (pin "3") (pinfunction "DO_3") (pintype "output"))
      (node (ref "LED9") (pin "1") (pinfunction "DI_1") (pintype "input"))
      (node (ref "R10") (pin "2") (pinfunction "2_2") (pintype "passive"))
      (node (ref "R11") (pin "1") (pinfunction "1_1") (pintype "passive"))
    )
    (net (code "32") (name "Net-(LED10-DI)") (class "Default")
      (node (ref "LED10") (pin "1") (pinfunction "DI_1") (pintype "input"))
      (node (ref "LED9") (pin "3") (pinfunction "DO_3") (pintype "output"))
      (node (ref "R11") (pin "2") (pinfunction "2_2") (pintype "passive"))
      (node (ref "R12") (pin "1") (pinfunction "1_1") (pintype "passive"))
    )
    (net (code "33") (name "Net-(LED10-DO)") (class "Default")
      (node (ref "LED10") (pin "3") (pinfunction "DO_3") (pintype "output"))
      (node (ref "LED11") (pin "1") (pinfunction "DI_1") (pintype "input"))
      (node (ref "R12") (pin "2") (pinfunction "2_2") (pintype "passive"))
      (node (ref "R13") (pin "1") (pinfunction "1_1") (pintype "passive"))
    )
    (net (code "34") (name "Net-(LED11-DO)") (class "Default")
      (node (ref "LED11") (pin "3") (pinfunction "DO_3") (pintype "output"))
      (node (ref "LED12") (pin "1") (pinfunction "DI_1") (pintype "input"))
      (node (ref "R13") (pin "2") (pinfunction "2_2") (pintype "passive"))
      (node (ref "R14") (pin "1") (pinfunction "1_1") (pintype "passive"))
    )
    (net (code "35") (name "Net-(LED12-DO)") (class "Default")
      (node (ref "LED12") (pin "3") (pinfunction "DO_3") (pintype "output"))
      (node (ref "LED13") (pin "1") (pinfunction "DI_1") (pintype "input"))
      (node (ref "R14") (pin "2") (pinfunction "2_2") (pintype "passive"))
      (node (ref "R15") (pin "1") (pinfunction "1_1") (pintype "passive"))
    )
    (net (code "36") (name "Net-(LED13-DO)") (class "Default")
      (node (ref "LED13") (pin "3") (pinfunction "DO_3") (pintype "output"))
      (node (ref "LED14") (pin "1") (pinfunction "DI_1") (pintype "input"))
      (node (ref "R1") (pin "1") (pinfunction "1_1") (pintype "passive"))
      (node (ref "R15") (pin "2") (pinfunction "2_2") (pintype "passive"))
    )
    (net (code "37") (name "Net-(LED14-DO)") (class "Default")
      (node (ref "LED14") (pin "3") (pinfunction "DO_3") (pintype "output"))
      (node (ref "LED15") (pin "1") (pinfunction "DI_1") (pintype "input"))
      (node (ref "R1") (pin "2") (pinfunction "2_2") (pintype "passive"))
      (node (ref "R2") (pin "1") (pinfunction "1_1") (pintype "passive"))
    )
    (net (code "38") (name "Net-(LED16-DO)") (class "Default")
      (node (ref "LED16") (pin "3") (pinfunction "DO_3") (pintype "output"))
      (node (ref "LED18") (pin "1") (pinfunction "DI_1") (pintype "input"))
      (node (ref "R26") (pin "1") (pinfunction "1_1") (pintype "passive"))
      (node (ref "R30") (pin "1") (pinfunction "1_1") (pintype "passive"))
    )
    (net (code "39") (name "Net-(LED17-DI)") (class "Default")
      (node (ref "LED17") (pin "1") (pinfunction "DI_1") (pintype "input"))
      (node (ref "LED19") (pin "3") (pinfunction "DO_3") (pintype "output"))
      (node (ref "R29") (pin "2") (pinfunction "2_2") (pintype "passive"))
      (node (ref "R31") (pin "1") (pinfunction "1_1") (pintype "passive"))
    )
    (net (code "40") (name "Net-(LED18-DO)") (class "Default")
      (node (ref "LED18") (pin "3") (pinfunction "DO_3") (pintype "output"))
      (node (ref "LED19") (pin "1") (pinfunction "DI_1") (pintype "input"))
      (node (ref "R26") (pin "2") (pinfunction "2_2") (pintype "passive"))
      (node (ref "R29") (pin "1") (pinfunction "1_1") (pintype "passive"))
    )
    (net (code "41") (name "Net-(LED31-DO)") (class "Default")
      (node (ref "LED31") (pin "3") (pinfunction "DO_3") (pintype "output"))
      (node (ref "LED32") (pin "1") (pinfunction "DI_1") (pintype "input"))
      (node (ref "R50") (pin "2") (pinfunction "2_2") (pintype "passive"))
      (node (ref "R51") (pin "1") (pinfunction "1_1") (pintype "passive"))
    )
    (net (code "42") (name "Net-(LED32-DO)") (class "Default")
      (node (ref "LED32") (pin "3") (pinfunction "DO_3") (pintype "output"))
      (node (ref "LED33") (pin "1") (pinfunction "DI_1") (pintype "input"))
      (node (ref "R51") (pin "2") (pinfunction "2_2") (pintype "passive"))
      (node (ref "R52") (pin "1") (pinfunction "1_1") (pintype "passive"))
    )
    (net (code "43") (name "Net-(LED33-DO)") (class "Default")
      (node (ref "LED33") (pin "3") (pinfunction "DO_3") (pintype "output"))
      (node (ref "LED34") (pin "1") (pinfunction "DI_1") (pintype "input"))
      (node (ref "R52") (pin "2") (pinfunction "2_2") (pintype "passive"))
      (node (ref "R53") (pin "1") (pinfunction "1_1") (pintype "passive"))
    )
    (net (code "44") (name "Net-(LED34-DO)") (class "Default")
      (node (ref "LED34") (pin "3") (pinfunction "DO_3") (pintype "output"))
      (node (ref "LED35") (pin "1") (pinfunction "DI_1") (pintype "input"))
      (node (ref "R53") (pin "2") (pinfunction "2_2") (pintype "passive"))
      (node (ref "R54") (pin "1") (pinfunction "1_1") (pintype "passive"))
    )
    (net (code "45") (name "Net-(LED35-DO)") (class "Default")
      (node (ref "LED35") (pin "3") (pinfunction "DO_3") (pintype "output"))
      (node (ref "LED36") (pin "1") (pinfunction "DI_1") (pintype "input"))
      (node (ref "R54") (pin "2") (pinfunction "2_2") (pintype "passive"))
      (node (ref "R55") (pin "1") (pinfunction "1_1") (pintype "passive"))
    )
    (net (code "46") (name "Net-(LED36-DO)") (class "Default")
      (node (ref "LED36") (pin "3") (pinfunction "DO_3") (pintype "output"))
      (node (ref "LED37") (pin "1") (pinfunction "DI_1") (pintype "input"))
      (node (ref "R41") (pin "1") (pinfunction "1_1") (pintype "passive"))
      (node (ref "R55") (pin "2") (pinfunction "2_2") (pintype "passive"))
    )
    (net (code "47") (name "Net-(LED37-DO)") (class "Default")
      (node (ref "LED37") (pin "3") (pinfunction "DO_3") (pintype "output"))
      (node (ref "LED38") (pin "1") (pinfunction "DI_1") (pintype "input"))
      (node (ref "R41") (pin "2") (pinfunction "2_2") (pintype "passive"))
      (node (ref "R42") (pin "1") (pinfunction "1_1") (pintype "passive"))
    )
    (net (code "48") (name "Net-(LED38-DO)") (class "Default")
      (node (ref "LED38") (pin "3") (pinfunction "DO_3") (pintype "output"))
      (node (ref "LED39") (pin "1") (pinfunction "DI_1") (pintype "input"))
      (node (ref "R42") (pin "2") (pinfunction "2_2") (pintype "passive"))
      (node (ref "R43") (pin "1") (pinfunction "1_1") (pintype "passive"))
    )
    (net (code "49") (name "Net-(LED39-DO)") (class "Default")
      (node (ref "LED39") (pin "3") (pinfunction "DO_3") (pintype "output"))
      (node (ref "LED40") (pin "1") (pinfunction "DI_1") (pintype "input"))
      (node (ref "R43") (pin "2") (pinfunction "2_2") (pintype "passive"))
      (node (ref "R44") (pin "1") (pinfunction "1_1") (pintype "passive"))
    )
    (net (code "50") (name "Net-(LED40-DO)") (class "Default")
      (node (ref "LED40") (pin "3") (pinfunction "DO_3") (pintype "output"))
      (node (ref "LED41") (pin "1") (pinfunction "DI_1") (pintype "input"))
      (node (ref "R44") (pin "2") (pinfunction "2_2") (pintype "passive"))
      (node (ref "R45") (pin "1") (pinfunction "1_1") (pintype "passive"))
    )
    (net (code "51") (name "Net-(LED41-DO)") (class "Default")
      (node (ref "LED41") (pin "3") (pinfunction "DO_3") (pintype "output"))
      (node (ref "LED42") (pin "1") (pinfunction "DI_1") (pintype "input"))
      (node (ref "R45") (pin "2") (pinfunction "2_2") (pintype "passive"))
      (node (ref "R46") (pin "1") (pinfunction "1_1") (pintype "passive"))
    )
    (net (code "52") (name "Net-(LED42-DO)") (class "Default")
      (node (ref "LED42") (pin "3") (pinfunction "DO_3") (pintype "output"))
      (node (ref "LED43") (pin "1") (pinfunction "DI_1") (pintype "input"))
      (node (ref "R46") (pin "2") (pinfunction "2_2") (pintype "passive"))
      (node (ref "R47") (pin "1") (pinfunction "1_1") (pintype "passive"))
    )
    (net (code "53") (name "Net-(LED43-DO)") (class "Default")
      (node (ref "LED43") (pin "3") (pinfunction "DO_3") (pintype "output"))
      (node (ref "LED44") (pin "1") (pinfunction "DI_1") (pintype "input"))
      (node (ref "R47") (pin "2") (pinfunction "2_2") (pintype "passive"))
      (node (ref "R48") (pin "1") (pinfunction "1_1") (pintype "passive"))
    )
    (net (code "54") (name "Net-(LED44-DO)") (class "Default")
      (node (ref "LED44") (pin "3") (pinfunction "DO_3") (pintype "output"))
      (node (ref "LED45") (pin "1") (pinfunction "DI_1") (pintype "input"))
      (node (ref "R48") (pin "2") (pinfunction "2_2") (pintype "passive"))
      (node (ref "R49") (pin "1") (pinfunction "1_1") (pintype "passive"))
    )
    (net (code "55") (name "PAD") (class "Default")
      (node (ref "R16") (pin "1") (pinfunction "1_1") (pintype "passive"))
    )
    (net (code "56") (name "POT") (class "Default")
      (node (ref "JP1") (pin "2") (pinfunction "2_2") (pintype "passive"))
      (node (ref "R25") (pin "2") (pinfunction "S_2") (pintype "passive"))
      (node (ref "R27") (pin "1") (pinfunction "1_1") (pintype "passive"))
      (node (ref "R34") (pin "1") (pinfunction "1_1") (pintype "passive"))
      (node (ref "R36") (pin "2") (pinfunction "2_2") (pintype "passive"))
      (node (ref "R37") (pin "2") (pinfunction "2_2") (pintype "passive"))
      (node (ref "S1") (pin "SIG1") (pinfunction "SIG1_SIG1") (pintype "bidirectional"))
    )
    (net (code "57") (name "POT+") (class "Default")
      (node (ref "R23") (pin "1") (pinfunction "1_1") (pintype "passive"))
      (node (ref "R25") (pin "1") (pinfunction "A_1") (pintype "passive"))
    )
    (net (code "58") (name "RST") (class "Default")
      (node (ref "SL1") (pin "1") (pinfunction "1_1") (pintype "passive"))
      (node (ref "U$1") (pin "1") (pinfunction "1_1") (pintype "passive"))
    )
    (net (code "59") (name "RXD") (class "Default")
      (node (ref "CN1") (pin "4") (pinfunction "4_4") (pintype "bidirectional"))
      (node (ref "SH1") (pin "P$2") (pinfunction "P$2_P$2") (pintype "bidirectional"))
    )
    (net (code "60") (name "SCK") (class "Default")
      (node (ref "IC1") (pin "17") (pinfunction "PB5(SCK)_17") (pintype "bidirectional"))
      (node (ref "R20") (pin "1") (pinfunction "1_1") (pintype "passive"))
      (node (ref "SL1") (pin "4") (pinfunction "4_4") (pintype "passive"))
      (node (ref "SL2") (pin "1") (pinfunction "1_1") (pintype "passive"))
      (node (ref "U$1") (pin "4") (pinfunction "4_4") (pintype "passive"))
      (node (ref "X2") (pin "6") (pinfunction "S_6") (pintype "passive"))
      (node (ref "X4") (pin "4") (pinfunction "SCK_4") (pintype "bidirectional"))
      (node (ref "X5") (pin "1") (pinfunction "S_1") (pintype "passive"))
    )
    (net (code "61") (name "SCL") (class "Default")
      (node (ref "IC1") (pin "28") (pinfunction "PC5(ADC5/SCL)_28") (pintype "bidirectional"))
      (node (ref "SL2") (pin "5") (pinfunction "5_5") (pintype "passive"))
      (node (ref "X2") (pin "2") (pinfunction "S_2") (pintype "passive"))
      (node (ref "X5") (pin "5") (pinfunction "S_5") (pintype "passive"))
    )
    (net (code "62") (name "SDA") (class "Default")
      (node (ref "IC1") (pin "27") (pinfunction "PC4(ADC4/SDA)_27") (pintype "bidirectional"))
      (node (ref "SL2") (pin "6") (pinfunction "6_6") (pintype "passive"))
      (node (ref "X2") (pin "1") (pinfunction "S_1") (pintype "passive"))
      (node (ref "X5") (pin "6") (pinfunction "S_6") (pintype "passive"))
    )
    (net (code "63") (name "SW1") (class "Default")
      (node (ref "IC1") (pin "23") (pinfunction "PC0(ADC0)_23") (pintype "bidirectional"))
      (node (ref "R24") (pin "2") (pinfunction "2_2") (pintype "passive"))
      (node (ref "R27") (pin "2") (pinfunction "2_2") (pintype "passive"))
      (node (ref "R28") (pin "2") (pinfunction "2_2") (pintype "passive"))
      (node (ref "RN2") (pin "5") (pinfunction "5_5") (pintype "passive"))
      (node (ref "RN3") (pin "7") (pinfunction "7_7") (pintype "passive"))
    )
    (net (code "64") (name "SWL") (class "Default")
      (node (ref "IC1") (pin "24") (pinfunction "PC1(ADC1)_24") (pintype "bidirectional"))
      (node (ref "RN2") (pin "6") (pinfunction "6_6") (pintype "passive"))
      (node (ref "RN3") (pin "8") (pinfunction "8_8") (pintype "passive"))
      (node (ref "X1") (pin "6") (pinfunction "S_6") (pintype "passive"))
    )
    (net (code "65") (name "SWR") (class "Default")
      (node (ref "IC1") (pin "25") (pinfunction "PC2(ADC2)_25") (pintype "bidirectional"))
      (node (ref "RN2") (pin "3") (pinfunction "3_3") (pintype "passive"))
      (node (ref "RN2") (pin "4") (pinfunction "4_4") (pintype "passive"))
      (node (ref "RN3") (pin "1") (pinfunction "1_1") (pintype "passive"))
      (node (ref "RN3") (pin "2") (pinfunction "2_2") (pintype "passive"))
      (node (ref "X3") (pin "1") (pinfunction "S_1") (pintype "passive"))
    )
    (net (code "66") (name "TOUCH") (class "Default")
      (node (ref "IC1") (pin "11") (pinfunction "PD7(AIN1)_11") (pintype "bidirectional"))
      (node (ref "IC2") (pin "1") (pinfunction "OUT_1") (pintype "bidirectional"))
      (node (ref "R24") (pin "1") (pinfunction "1_1") (pintype "passive"))
      (node (ref "R38") (pin "2") (pinfunction "2_2") (pintype "passive"))
      (node (ref "R39") (pin "2") (pinfunction "2_2") (pintype "passive"))
    )
    (net (code "67") (name "TXD") (class "Default")
      (node (ref "CN1") (pin "5") (pinfunction "5_5") (pintype "bidirectional"))
      (node (ref "SH2") (pin "P$2") (pinfunction "P$2_P$2") (pintype "bidirectional"))
    )
    (net (code "68") (name "VCC") (class "Default")
      (node (ref "C1") (pin "1") (pinfunction "1_1") (pintype "passive"))
      (node (ref "C10") (pin "1") (pinfunction "1_1") (pintype "passive"))
      (node (ref "C11") (pin "1") (pinfunction "1_1") (pintype "passive"))
      (node (ref "C12") (pin "1") (pinfunction "1_1") (pintype "passive"))
      (node (ref "C13") (pin "1") (pinfunction "1_1") (pintype "passive"))
      (node (ref "C14") (pin "1") (pinfunction "1_1") (pintype "passive"))
      (node (ref "C15") (pin "1") (pinfunction "1_1") (pintype "passive"))
      (node (ref "C17") (pin "1") (pinfunction "1_1") (pintype "passive"))
      (node (ref "C19") (pin "+") (pinfunction "+_+") (pintype "passive"))
      (node (ref "C2") (pin "1") (pinfunction "1_1") (pintype "passive"))
      (node (ref "C20") (pin "1") (pinfunction "1_1") (pintype "passive"))
      (node (ref "C21") (pin "1") (pinfunction "1_1") (pintype "passive"))
      (node (ref "C22") (pin "1") (pinfunction "1_1") (pintype "passive"))
      (node (ref "C23") (pin "1") (pinfunction "1_1") (pintype "passive"))
      (node (ref "C24") (pin "1") (pinfunction "1_1") (pintype "passive"))
      (node (ref "C26") (pin "1") (pinfunction "1_1") (pintype "passive"))
      (node (ref "C3") (pin "1") (pinfunction "1_1") (pintype "passive"))
      (node (ref "C4") (pin "1") (pinfunction "1_1") (pintype "passive"))
      (node (ref "C41") (pin "1") (pinfunction "1_1") (pintype "passive"))
      (node (ref "C42") (pin "1") (pinfunction "1_1") (pintype "passive"))
      (node (ref "C43") (pin "1") (pinfunction "1_1") (pintype "passive"))
      (node (ref "C44") (pin "1") (pinfunction "1_1") (pintype "passive"))
      (node (ref "C45") (pin "1") (pinfunction "1_1") (pintype "passive"))
      (node (ref "C46") (pin "1") (pinfunction "1_1") (pintype "passive"))
      (node (ref "C47") (pin "1") (pinfunction "1_1") (pintype "passive"))
      (node (ref "C48") (pin "1") (pinfunction "1_1") (pintype "passive"))
      (node (ref "C49") (pin "1") (pinfunction "1_1") (pintype "passive"))
      (node (ref "C5") (pin "1") (pinfunction "1_1") (pintype "passive"))
      (node (ref "C50") (pin "1") (pinfunction "1_1") (pintype "passive"))
      (node (ref "C51") (pin "1") (pinfunction "1_1") (pintype "passive"))
      (node (ref "C52") (pin "1") (pinfunction "1_1") (pintype "passive"))
      (node (ref "C53") (pin "1") (pinfunction "1_1") (pintype "passive"))
      (node (ref "C54") (pin "1") (pinfunction "1_1") (pintype "passive"))
      (node (ref "C55") (pin "1") (pinfunction "1_1") (pintype "passive"))
      (node (ref "C6") (pin "1") (pinfunction "1_1") (pintype "passive"))
      (node (ref "C7") (pin "1") (pinfunction "1_1") (pintype "passive"))
      (node (ref "C8") (pin "1") (pinfunction "1_1") (pintype "passive"))
      (node (ref "C9") (pin "1") (pinfunction "1_1") (pintype "passive"))
      (node (ref "CN1") (pin "3") (pinfunction "3_3") (pintype "bidirectional"))
      (node (ref "IC1") (pin "18") (pinfunction "AVCC_18") (pintype "power_in"))
      (node (ref "IC1") (pin "4") (pinfunction "VCC_4") (pintype "power_in"))
      (node (ref "IC1") (pin "6") (pinfunction "VCC_6") (pintype "power_in"))
      (node (ref "IC2") (pin "5") (pinfunction "VDD_5") (pintype "bidirectional"))
      (node (ref "J1") (pin "1") (pinfunction "1_1") (pintype "passive"))
      (node (ref "J10") (pin "1") (pinfunction "1_1") (pintype "passive"))
      (node (ref "J11") (pin "1") (pinfunction "1_1") (pintype "passive"))
      (node (ref "J12") (pin "1") (pinfunction "1_1") (pintype "passive"))
      (node (ref "J13") (pin "1") (pinfunction "1_1") (pintype "passive"))
      (node (ref "J14") (pin "1") (pinfunction "1_1") (pintype "passive"))
      (node (ref "J2") (pin "1") (pinfunction "1_1") (pintype "passive"))
      (node (ref "J3") (pin "1") (pinfunction "1_1") (pintype "passive"))
      (node (ref "J4") (pin "1") (pinfunction "1_1") (pintype "passive"))
      (node (ref "J5") (pin "1") (pinfunction "1_1") (pintype "passive"))
      (node (ref "J6") (pin "1") (pinfunction "1_1") (pintype "passive"))
      (node (ref "J7") (pin "1") (pinfunction "1_1") (pintype "passive"))
      (node (ref "JP5") (pin "1") (pinfunction "1_1") (pintype "passive"))
      (node (ref "LED1") (pin "2") (pinfunction "VDD_2") (pintype "power_in"))
      (node (ref "LED10") (pin "2") (pinfunction "VDD_2") (pintype "power_in"))
      (node (ref "LED11") (pin "2") (pinfunction "VDD_2") (pintype "power_in"))
      (node (ref "LED12") (pin "2") (pinfunction "VDD_2") (pintype "power_in"))
      (node (ref "LED13") (pin "2") (pinfunction "VDD_2") (pintype "power_in"))
      (node (ref "LED14") (pin "2") (pinfunction "VDD_2") (pintype "power_in"))
      (node (ref "LED15") (pin "2") (pinfunction "VDD_2") (pintype "power_in"))
      (node (ref "LED16") (pin "2") (pinfunction "VDD_2") (pintype "power_in"))
      (node (ref "LED17") (pin "2") (pinfunction "VDD_2") (pintype "power_in"))
      (node (ref "LED18") (pin "2") (pinfunction "VDD_2") (pintype "power_in"))
      (node (ref "LED19") (pin "2") (pinfunction "VDD_2") (pintype "power_in"))
      (node (ref "LED2") (pin "2") (pinfunction "VDD_2") (pintype "power_in"))
      (node (ref "LED3") (pin "2") (pinfunction "VDD_2") (pintype "power_in"))
      (node (ref "LED31") (pin "2") (pinfunction "VDD_2") (pintype "power_in"))
      (node (ref "LED32") (pin "2") (pinfunction "VDD_2") (pintype "power_in"))
      (node (ref "LED33") (pin "2") (pinfunction "VDD_2") (pintype "power_in"))
      (node (ref "LED34") (pin "2") (pinfunction "VDD_2") (pintype "power_in"))
      (node (ref "LED35") (pin "2") (pinfunction "VDD_2") (pintype "power_in"))
      (node (ref "LED36") (pin "2") (pinfunction "VDD_2") (pintype "power_in"))
      (node (ref "LED37") (pin "2") (pinfunction "VDD_2") (pintype "power_in"))
      (node (ref "LED38") (pin "2") (pinfunction "VDD_2") (pintype "power_in"))
      (node (ref "LED39") (pin "2") (pinfunction "VDD_2") (pintype "power_in"))
      (node (ref "LED4") (pin "2") (pinfunction "VDD_2") (pintype "power_in"))
      (node (ref "LED40") (pin "2") (pinfunction "VDD_2") (pintype "power_in"))
      (node (ref "LED41") (pin "2") (pinfunction "VDD_2") (pintype "power_in"))
      (node (ref "LED42") (pin "2") (pinfunction "VDD_2") (pintype "power_in"))
      (node (ref "LED43") (pin "2") (pinfunction "VDD_2") (pintype "power_in"))
      (node (ref "LED44") (pin "2") (pinfunction "VDD_2") (pintype "power_in"))
      (node (ref "LED45") (pin "2") (pinfunction "VDD_2") (pintype "power_in"))
      (node (ref "LED5") (pin "2") (pinfunction "VDD_2") (pintype "power_in"))
      (node (ref "LED6") (pin "2") (pinfunction "VDD_2") (pintype "power_in"))
      (node (ref "LED7") (pin "2") (pinfunction "VDD_2") (pintype "power_in"))
      (node (ref "LED8") (pin "2") (pinfunction "VDD_2") (pintype "power_in"))
      (node (ref "LED9") (pin "2") (pinfunction "VDD_2") (pintype "power_in"))
      (node (ref "POWER") (pin "9") (pinfunction "1_9") (pintype "passive"))
      (node (ref "R17") (pin "2") (pinfunction "2_2") (pintype "passive"))
      (node (ref "R23") (pin "2") (pinfunction "2_2") (pintype "passive"))
      (node (ref "R32") (pin "2") (pinfunction "2_2") (pintype "passive"))
      (node (ref "R33") (pin "2") (pinfunction "2_2") (pintype "passive"))
      (node (ref "R34") (pin "2") (pinfunction "2_2") (pintype "passive"))
      (node (ref "R35") (pin "2") (pinfunction "2_2") (pintype "passive"))
      (node (ref "SL1") (pin "6") (pinfunction "6_6") (pintype "passive"))
      (node (ref "U$1") (pin "6") (pinfunction "6_6") (pintype "passive"))
      (node (ref "X4") (pin "6") (pinfunction "VCC_6") (pintype "bidirectional"))
    )
    (net (code "69") (name "unconnected-(IC1-ADC6-Pad19)") (class "Default")
      (node (ref "IC1") (pin "19") (pinfunction "ADC6_19") (pintype "bidirectional"))
    )
    (net (code "70") (name "unconnected-(IC1-ADC7-Pad22)") (class "Default")
      (node (ref "IC1") (pin "22") (pinfunction "ADC7_22") (pintype "bidirectional"))
    )
    (net (code "71") (name "unconnected-(RN1-Pad4)") (class "Default")
      (node (ref "RN1") (pin "4") (pinfunction "4_4") (pintype "passive"))
    )
    (net (code "72") (name "unconnected-(RN1-Pad5)") (class "Default")
      (node (ref "RN1") (pin "5") (pinfunction "5_5") (pintype "passive"))
    )
    (net (code "73") (name "unconnected-(RN4-Pad4)") (class "Default")
      (node (ref "RN4") (pin "4") (pinfunction "4_4") (pintype "passive"))
    )
    (net (code "74") (name "unconnected-(RN4-Pad5)") (class "Default")
      (node (ref "RN4") (pin "5") (pinfunction "5_5") (pintype "passive"))
    )
    (net (code "75") (name "~{RESET}") (class "Default")
      (node (ref "C18") (pin "2") (pinfunction "2_2") (pintype "passive"))
      (node (ref "IC1") (pin "29") (pinfunction "PC6(/RESET)_29") (pintype "bidirectional"))
      (node (ref "R17") (pin "1") (pinfunction "1_1") (pintype "passive"))
      (node (ref "X4") (pin "1") (pinfunction "\\RST_1") (pintype "bidirectional"))
    )
    (net (code "76") (name "~{SS}") (class "Default")
      (node (ref "IC1") (pin "14") (pinfunction "PB2(SS/OC1B)_14") (pintype "bidirectional"))
      (node (ref "SL2") (pin "4") (pinfunction "4_4") (pintype "passive"))
      (node (ref "X2") (pin "3") (pinfunction "S_3") (pintype "passive"))
      (node (ref "X5") (pin "4") (pinfunction "S_4") (pintype "passive"))
    )
  )
)
